# brushless_module_v1.net
KiCad netlist of a schematic drawn in EAGLE
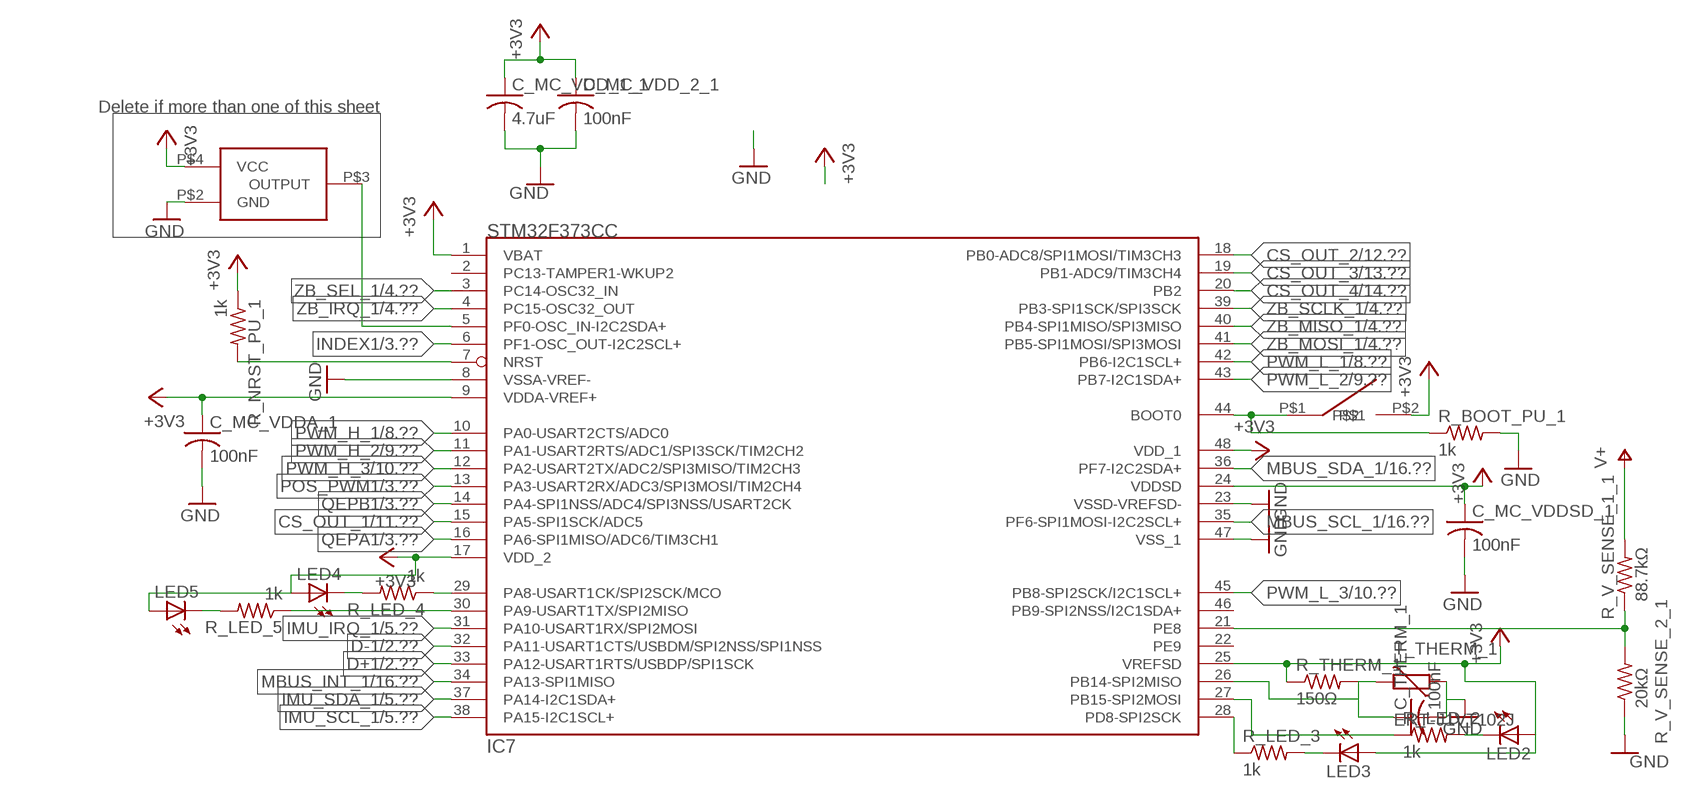
[diagram p0: schematic, sheet 1]
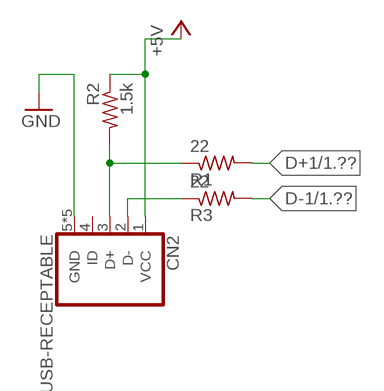
[diagram p1: schematic, sheet 2]
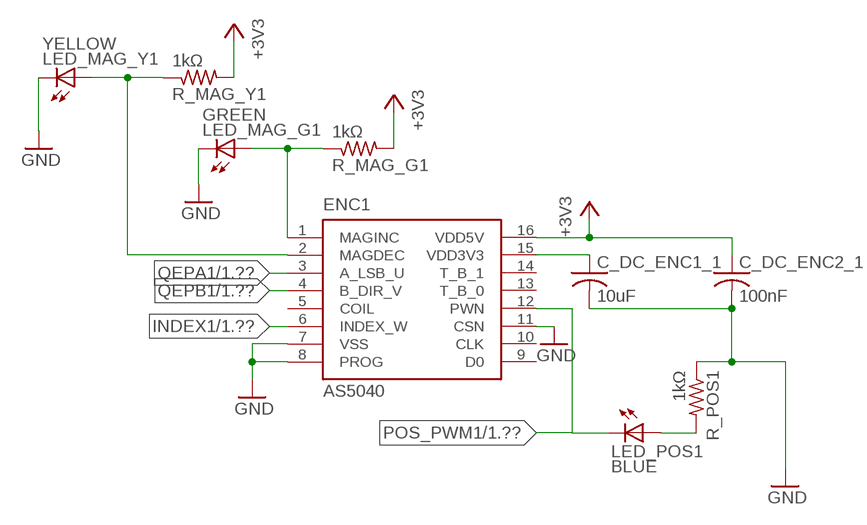
[diagram p2: schematic, sheet 3]
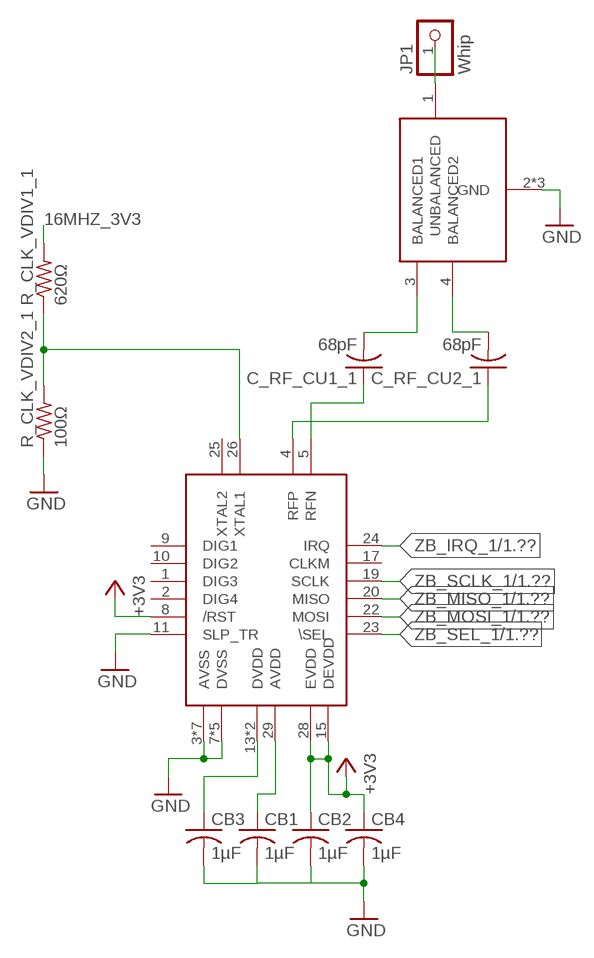
[diagram p3: schematic, sheet 4]
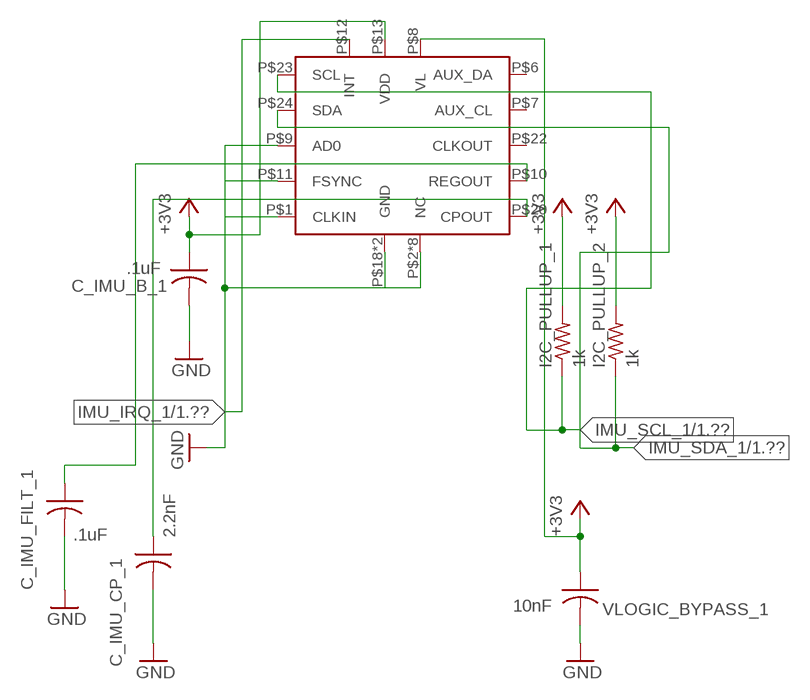
[diagram p4: schematic, sheet 5]
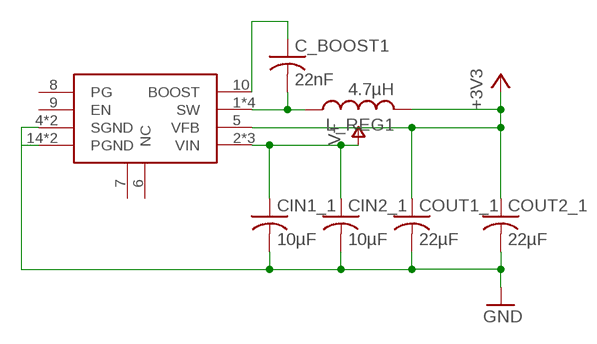
[diagram p5: schematic, sheet 6]
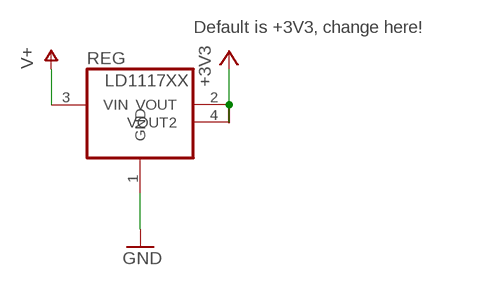
[diagram p6: schematic, sheet 7]
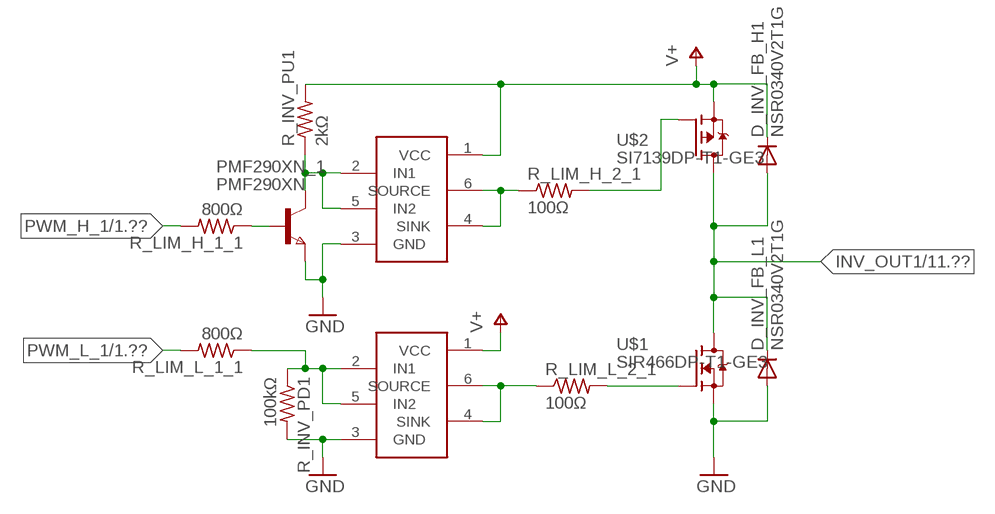
[diagram p7: schematic, sheet 8]
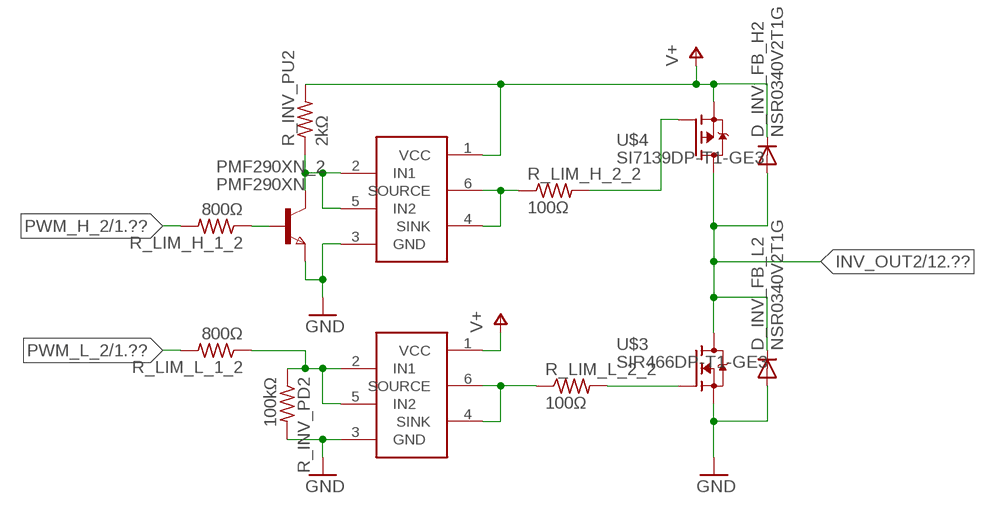
[diagram p8: schematic, sheet 9]
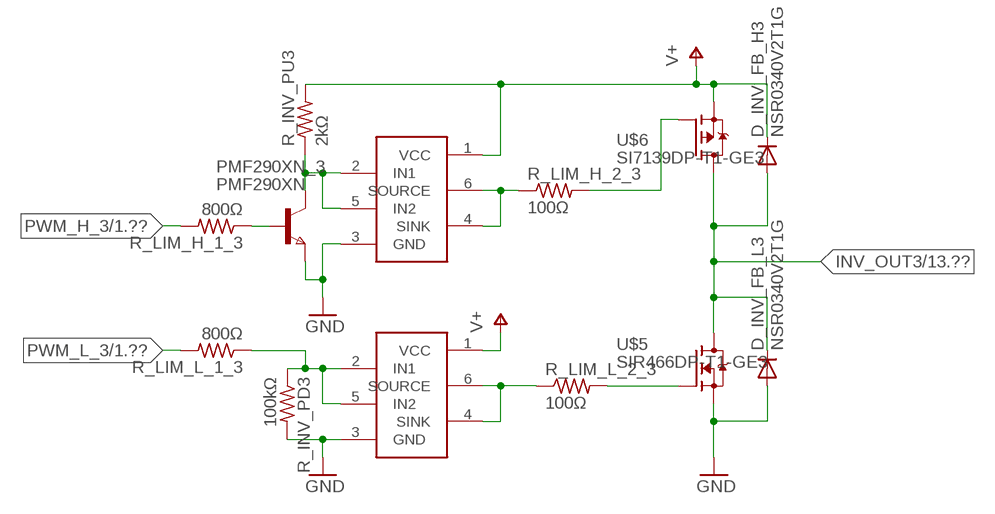
[diagram p9: schematic, sheet 10]
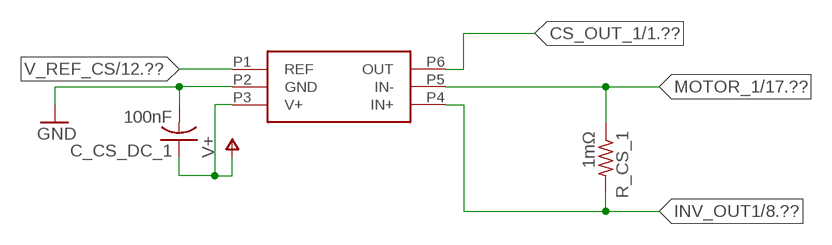
[diagram p10: schematic, sheet 11]
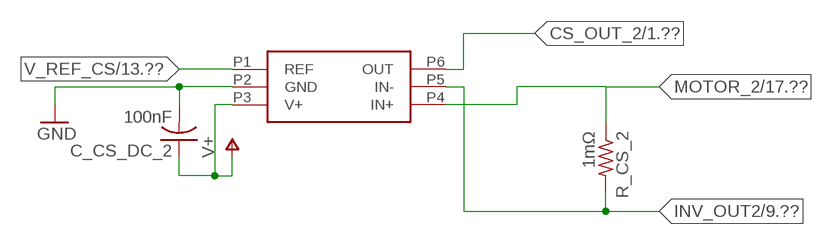
[diagram p11: schematic, sheet 12]
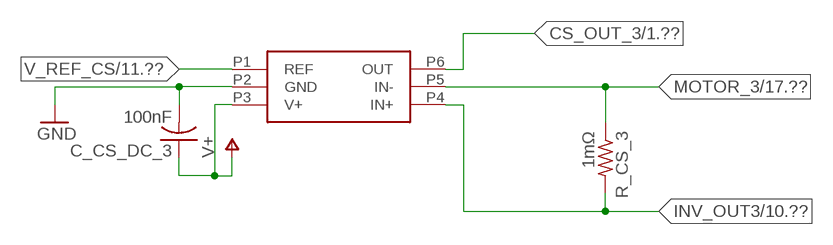
[diagram p12: schematic, sheet 13]
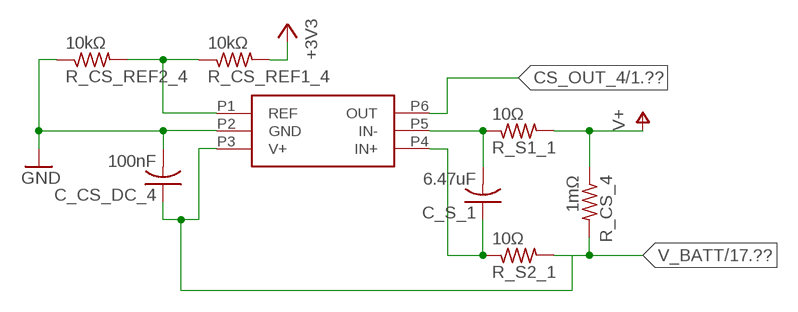
[diagram p13: schematic, sheet 14]
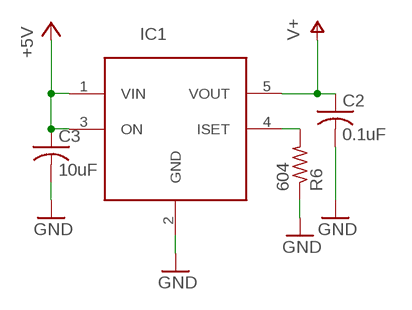
[diagram p14: schematic, sheet 15]
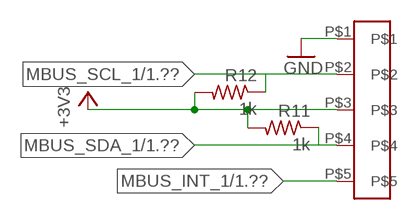
[diagram p15: schematic, sheet 16]
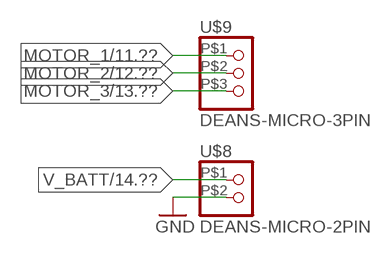
[diagram p16: schematic, sheet 17]

(export (version "E")
  (design (tool "Eeschema 10.0.6"))
  (components
    (comp (ref "CS_3")
      (value "INA21X")
      (footprint "eagle-import:SC70")
      (libsource (lib "eagle-import") (part "INA21X"))
    )
    (comp (ref "C_CS_DC_3")
      (value "100nF")
      (footprint "eagle-import:C0603")
      (libsource (lib "eagle-import") (part "C-USC0603"))
    )
    (comp (ref "R_CS_3")
      (value "1mΩ")
      (footprint "eagle-import:R1206")
      (libsource (lib "eagle-import") (part "R-US_R1206"))
    )
    (comp (ref "D_INV_FB_H3")
      (value "NSR0340V2T1G")
      (footprint "eagle-import:SOD523")
      (libsource (lib "eagle-import") (part "DIODE-SOD523"))
    )
    (comp (ref "D_INV_FB_L3")
      (value "NSR0340V2T1G")
      (footprint "eagle-import:SOD523")
      (libsource (lib "eagle-import") (part "DIODE-SOD523"))
    )
    (comp (ref "PMF290XN_3")
      (value "PMF290XN")
      (footprint "eagle-import:SOT323")
      (libsource (lib "eagle-import") (part "NPNSOT323"))
    )
    (comp (ref "R_INV_PD3")
      (value "100kΩ")
      (footprint "eagle-import:R0603")
      (fields (field (name "PART#") "RNCP0603FTD825RCT-ND"))
      (libsource (lib "eagle-import") (part "R-US_R0603"))
    )
    (comp (ref "R_INV_PU3")
      (value "2kΩ")
      (footprint "eagle-import:R0603")
      (libsource (lib "eagle-import") (part "R-US_R0603"))
    )
    (comp (ref "R_LIM_H_1_3")
      (value "800Ω")
      (footprint "eagle-import:R0603")
      (libsource (lib "eagle-import") (part "R-US_R0603"))
    )
    (comp (ref "R_LIM_H_2_3")
      (value "100Ω")
      (footprint "eagle-import:R0603")
      (libsource (lib "eagle-import") (part "R-US_R0603"))
    )
    (comp (ref "R_LIM_L_1_3")
      (value "800Ω")
      (footprint "eagle-import:R0603")
      (libsource (lib "eagle-import") (part "R-US_R0603"))
    )
    (comp (ref "R_LIM_L_2_3")
      (value "100Ω")
      (footprint "eagle-import:R0603")
      (libsource (lib "eagle-import") (part "R-US_R0603"))
    )
    (comp (ref "U$5")
      (value "SIR466DP-T1-GE3")
      (footprint "eagle-import:S0-8-POWERPAK")
      (libsource (lib "eagle-import") (part "SIR466DP-T1-GE3"))
    )
    (comp (ref "U$6")
      (value "SI7139DP-T1-GE3")
      (footprint "eagle-import:S0-8-POWERPAK")
      (libsource (lib "eagle-import") (part "SI7139DP-T1-GE3"))
    )
    (comp (ref "ZXGD3004E6_H_3")
      (value "ZXGD3004E6")
      (footprint "eagle-import:SOT23-6")
      (libsource (lib "eagle-import") (part "ZXGD3004E6"))
    )
    (comp (ref "ZXGD3004E6_L_3")
      (value "ZXGD3004E6")
      (footprint "eagle-import:SOT23-6")
      (libsource (lib "eagle-import") (part "ZXGD3004E6"))
    )
    (comp (ref "CN2")
      (value "USB-RECEPTABLE")
      (footprint "eagle-import:FCI-10103594-0001LF")
      (libsource (lib "eagle-import") (part "USB-RECEPTABLE"))
    )
    (comp (ref "R1")
      (value "22")
      (footprint "eagle-import:R0603")
      (libsource (lib "eagle-import") (part "R-US_R0603"))
    )
    (comp (ref "R2")
      (value "1.5k")
      (footprint "eagle-import:R0603")
      (libsource (lib "eagle-import") (part "R-US_R0603"))
    )
    (comp (ref "R3")
      (value "22")
      (footprint "eagle-import:R0603")
      (libsource (lib "eagle-import") (part "R-US_R0603"))
    )
    (comp (ref "D_INV_FB_H2")
      (value "NSR0340V2T1G")
      (footprint "eagle-import:SOD523")
      (libsource (lib "eagle-import") (part "DIODE-SOD523"))
    )
    (comp (ref "D_INV_FB_L2")
      (value "NSR0340V2T1G")
      (footprint "eagle-import:SOD523")
      (libsource (lib "eagle-import") (part "DIODE-SOD523"))
    )
    (comp (ref "PMF290XN_2")
      (value "PMF290XN")
      (footprint "eagle-import:SOT323")
      (libsource (lib "eagle-import") (part "NPNSOT323"))
    )
    (comp (ref "R_INV_PD2")
      (value "100kΩ")
      (footprint "eagle-import:R0603")
      (fields (field (name "PART#") "RNCP0603FTD825RCT-ND"))
      (libsource (lib "eagle-import") (part "R-US_R0603"))
    )
    (comp (ref "R_INV_PU2")
      (value "2kΩ")
      (footprint "eagle-import:R0603")
      (libsource (lib "eagle-import") (part "R-US_R0603"))
    )
    (comp (ref "R_LIM_H_1_2")
      (value "800Ω")
      (footprint "eagle-import:R0603")
      (libsource (lib "eagle-import") (part "R-US_R0603"))
    )
    (comp (ref "R_LIM_H_2_2")
      (value "100Ω")
      (footprint "eagle-import:R0603")
      (libsource (lib "eagle-import") (part "R-US_R0603"))
    )
    (comp (ref "R_LIM_L_1_2")
      (value "800Ω")
      (footprint "eagle-import:R0603")
      (libsource (lib "eagle-import") (part "R-US_R0603"))
    )
    (comp (ref "R_LIM_L_2_2")
      (value "100Ω")
      (footprint "eagle-import:R0603")
      (libsource (lib "eagle-import") (part "R-US_R0603"))
    )
    (comp (ref "U$3")
      (value "SIR466DP-T1-GE3")
      (footprint "eagle-import:S0-8-POWERPAK")
      (libsource (lib "eagle-import") (part "SIR466DP-T1-GE3"))
    )
    (comp (ref "U$4")
      (value "SI7139DP-T1-GE3")
      (footprint "eagle-import:S0-8-POWERPAK")
      (libsource (lib "eagle-import") (part "SI7139DP-T1-GE3"))
    )
    (comp (ref "ZXGD3004E6_H_2")
      (value "ZXGD3004E6")
      (footprint "eagle-import:SOT23-6")
      (libsource (lib "eagle-import") (part "ZXGD3004E6"))
    )
    (comp (ref "ZXGD3004E6_L_2")
      (value "ZXGD3004E6")
      (footprint "eagle-import:SOT23-6")
      (libsource (lib "eagle-import") (part "ZXGD3004E6"))
    )
    (comp (ref "CS_2")
      (value "INA21X")
      (footprint "eagle-import:SC70")
      (libsource (lib "eagle-import") (part "INA21X"))
    )
    (comp (ref "C_CS_DC_2")
      (value "100nF")
      (footprint "eagle-import:C0603")
      (libsource (lib "eagle-import") (part "C-USC0603"))
    )
    (comp (ref "R_CS_2")
      (value "1mΩ")
      (footprint "eagle-import:R1206")
      (libsource (lib "eagle-import") (part "R-US_R1206"))
    )
    (comp (ref "C_DC_ENC1_1")
      (value "10uF")
      (footprint "eagle-import:C0603")
      (libsource (lib "eagle-import") (part "C-USC0603"))
    )
    (comp (ref "C_DC_ENC2_1")
      (value "100nF")
      (footprint "eagle-import:C0603")
      (libsource (lib "eagle-import") (part "C-USC0603"))
    )
    (comp (ref "ENC1")
      (value "AS5040")
      (footprint "eagle-import:SSOP16")
      (libsource (lib "eagle-import") (part "AS5040"))
    )
    (comp (ref "LED_MAG_G1")
      (value "GREEN")
      (footprint "eagle-import:CHIP-LED0603")
      (libsource (lib "eagle-import") (part "LEDCHIP-LED0603"))
    )
    (comp (ref "LED_MAG_Y1")
      (value "YELLOW")
      (footprint "eagle-import:CHIP-LED0603")
      (libsource (lib "eagle-import") (part "LEDCHIP-LED0603"))
    )
    (comp (ref "LED_POS1")
      (value "BLUE")
      (footprint "eagle-import:CHIP-LED0603")
      (libsource (lib "eagle-import") (part "LEDCHIP-LED0603"))
    )
    (comp (ref "R_MAG_G1")
      (value "1kΩ")
      (footprint "eagle-import:R0603")
      (libsource (lib "eagle-import") (part "R-US_R0603"))
    )
    (comp (ref "R_MAG_Y1")
      (value "1kΩ")
      (footprint "eagle-import:R0603")
      (libsource (lib "eagle-import") (part "R-US_R0603"))
    )
    (comp (ref "R_POS1")
      (value "1kΩ")
      (footprint "eagle-import:R0603")
      (libsource (lib "eagle-import") (part "R-US_R0603"))
    )
    (comp (ref "REG")
      (value "LD1117XX")
      (footprint "eagle-import:SOT-223")
      (libsource (lib "eagle-import") (part "LD1117XX"))
    )
    (comp (ref "CIN1_1")
      (value "10µF")
      (footprint "eagle-import:C0805")
      (libsource (lib "eagle-import") (part "C-USC0805"))
    )
    (comp (ref "CIN2_1")
      (value "10µF")
      (footprint "eagle-import:C0805")
      (libsource (lib "eagle-import") (part "C-USC0805"))
    )
    (comp (ref "COUT1_1")
      (value "22µF")
      (footprint "eagle-import:C0603")
      (libsource (lib "eagle-import") (part "C-USC0603"))
    )
    (comp (ref "COUT2_1")
      (value "22µF")
      (footprint "eagle-import:C0603")
      (libsource (lib "eagle-import") (part "C-USC0603"))
    )
    (comp (ref "C_BOOST1")
      (value "22nF")
      (footprint "eagle-import:C0603")
      (libsource (lib "eagle-import") (part "C-USC0603"))
    )
    (comp (ref "L_REG1")
      (value "4.7µH")
      (footprint "eagle-import:VLC5045")
      (libsource (lib "eagle-import") (part "VLC5045"))
    )
    (comp (ref "SW_REG1")
      (value "MCP16323")
      (footprint "eagle-import:QFN16")
      (libsource (lib "eagle-import") (part "MCP16323"))
    )
    (comp (ref "CS_4")
      (value "INA21X")
      (footprint "eagle-import:SC70")
      (libsource (lib "eagle-import") (part "INA21X"))
    )
    (comp (ref "C_CS_DC_4")
      (value "100nF")
      (footprint "eagle-import:C0603")
      (libsource (lib "eagle-import") (part "C-USC0603"))
    )
    (comp (ref "C_S_1")
      (value "6.47uF")
      (footprint "eagle-import:C0603")
      (libsource (lib "eagle-import") (part "C-USC0603"))
    )
    (comp (ref "R_CS_4")
      (value "1mΩ")
      (footprint "eagle-import:R1206")
      (libsource (lib "eagle-import") (part "R-US_R1206"))
    )
    (comp (ref "R_CS_REF1_4")
      (value "10kΩ")
      (footprint "eagle-import:R0603")
      (libsource (lib "eagle-import") (part "R-US_R0603"))
    )
    (comp (ref "R_CS_REF2_4")
      (value "10kΩ")
      (footprint "eagle-import:R0603")
      (libsource (lib "eagle-import") (part "R-US_R0603"))
    )
    (comp (ref "R_S1_1")
      (value "10Ω")
      (footprint "eagle-import:R0603")
      (libsource (lib "eagle-import") (part "R-US_R0603"))
    )
    (comp (ref "R_S2_1")
      (value "10Ω")
      (footprint "eagle-import:R0603")
      (libsource (lib "eagle-import") (part "R-US_R0603"))
    )
    (comp (ref "C_IMU_B_1")
      (value ".1uF")
      (footprint "eagle-import:C0603")
      (libsource (lib "eagle-import") (part "C-USC0603"))
    )
    (comp (ref "C_IMU_CP_1")
      (value "2.2nF")
      (footprint "eagle-import:C0603")
      (libsource (lib "eagle-import") (part "C-USC0603"))
    )
    (comp (ref "C_IMU_FILT_1")
      (value ".1uF")
      (footprint "eagle-import:C0603")
      (libsource (lib "eagle-import") (part "C-USC0603"))
    )
    (comp (ref "I2C_PULLUP_1")
      (value "1k")
      (footprint "eagle-import:R0603")
      (libsource (lib "eagle-import") (part "R-US_R0603"))
    )
    (comp (ref "I2C_PULLUP_2")
      (value "1k")
      (footprint "eagle-import:R0603")
      (libsource (lib "eagle-import") (part "R-US_R0603"))
    )
    (comp (ref "U$10")
      (value "MPU-6050")
      (footprint "eagle-import:QFN24")
      (libsource (lib "eagle-import") (part "MPU-6050"))
    )
    (comp (ref "VLOGIC_BYPASS_1")
      (value "10nF")
      (footprint "eagle-import:C0603")
      (libsource (lib "eagle-import") (part "C-USC0603"))
    )
    (comp (ref "U$8")
      (value "DEANS-MICRO-2PIN")
      (footprint "eagle-import:DEANS-MICRO-2PIN")
      (libsource (lib "eagle-import") (part "DEANS-MICRO-2PIN"))
    )
    (comp (ref "U$9")
      (value "DEANS-MICRO-3PIN")
      (footprint "eagle-import:DEANS-MICRO-3PIN")
      (libsource (lib "eagle-import") (part "DEANS-MICRO-3PIN"))
    )
    (comp (ref "C_MC_VDDA_1")
      (value "100nF")
      (footprint "eagle-import:C0603")
      (libsource (lib "eagle-import") (part "C-USC0603"))
    )
    (comp (ref "C_MC_VDDSD_1")
      (value "100nF")
      (footprint "eagle-import:C0603")
      (libsource (lib "eagle-import") (part "C-USC0603"))
    )
    (comp (ref "C_MC_VDD_1_1")
      (value "4.7uF")
      (footprint "eagle-import:C0603")
      (libsource (lib "eagle-import") (part "C-USC0603"))
    )
    (comp (ref "C_MC_VDD_2_1")
      (value "100nF")
      (footprint "eagle-import:C0603")
      (libsource (lib "eagle-import") (part "C-USC0603"))
    )
    (comp (ref "C_THERM_1")
      (value "100nF")
      (footprint "eagle-import:C0603")
      (libsource (lib "eagle-import") (part "C-USC0603"))
    )
    (comp (ref "IC7")
      (value "STM32F373CC")
      (footprint "eagle-import:LQFP48")
      (libsource (lib "eagle-import") (part "STM32F373CC"))
    )
    (comp (ref "LED2")
      (value "LEDCHIPLED_0603")
      (footprint "eagle-import:CHIPLED_0603")
      (libsource (lib "eagle-import") (part "LEDCHIPLED_0603"))
    )
    (comp (ref "LED3")
      (value "LEDCHIPLED_0603")
      (footprint "eagle-import:CHIPLED_0603")
      (libsource (lib "eagle-import") (part "LEDCHIPLED_0603"))
    )
    (comp (ref "LED4")
      (value "LEDCHIPLED_0603")
      (footprint "eagle-import:CHIPLED_0603")
      (libsource (lib "eagle-import") (part "LEDCHIPLED_0603"))
    )
    (comp (ref "LED5")
      (value "LEDCHIPLED_0603")
      (footprint "eagle-import:CHIPLED_0603")
      (libsource (lib "eagle-import") (part "LEDCHIPLED_0603"))
    )
    (comp (ref "OSC1")
      (value "FOX924B")
      (footprint "eagle-import:4-SMD_5X3.2")
      (libsource (lib "eagle-import") (part "FOX924B"))
    )
    (comp (ref "R_BOOT_PU_1")
      (value "1k")
      (footprint "eagle-import:R0603")
      (libsource (lib "eagle-import") (part "R-US_R0603"))
    )
    (comp (ref "R_LED_2")
      (value "1k")
      (footprint "eagle-import:R0603")
      (libsource (lib "eagle-import") (part "R-US_R0603"))
    )
    (comp (ref "R_LED_3")
      (value "1k")
      (footprint "eagle-import:R0603")
      (libsource (lib "eagle-import") (part "R-US_R0603"))
    )
    (comp (ref "R_LED_4")
      (value "1k")
      (footprint "eagle-import:R0603")
      (libsource (lib "eagle-import") (part "R-US_R0603"))
    )
    (comp (ref "R_LED_5")
      (value "1k")
      (footprint "eagle-import:R0603")
      (libsource (lib "eagle-import") (part "R-US_R0603"))
    )
    (comp (ref "R_NRST_PU_1")
      (value "1k")
      (footprint "eagle-import:R0603")
      (libsource (lib "eagle-import") (part "R-US_R0603"))
    )
    (comp (ref "R_THERM_1")
      (value "150Ω")
      (footprint "eagle-import:R0603")
      (libsource (lib "eagle-import") (part "R-US_R0603"))
    )
    (comp (ref "R_V_SENSE_1_1")
      (value "88.7kΩ")
      (footprint "eagle-import:R0603")
      (libsource (lib "eagle-import") (part "R-US_R0603"))
    )
    (comp (ref "R_V_SENSE_2_1")
      (value "20kΩ")
      (footprint "eagle-import:R0603")
      (libsource (lib "eagle-import") (part "R-US_R0603"))
    )
    (comp (ref "SW1")
      (value "B3U")
      (footprint "eagle-import:B3U")
      (libsource (lib "eagle-import") (part "B3U"))
    )
    (comp (ref "T_THERM_1")
      (value "ERT-J1VT102J")
      (footprint "eagle-import:CT_CN0603")
      (libsource (lib "eagle-import") (part "VARISTORCN0603"))
    )
    (comp (ref "C2")
      (value "0.1uF")
      (footprint "eagle-import:C0603")
      (libsource (lib "eagle-import") (part "C-USC0603"))
    )
    (comp (ref "C3")
      (value "10uF")
      (footprint "eagle-import:C0603")
      (libsource (lib "eagle-import") (part "C-USC0603"))
    )
    (comp (ref "IC1")
      (value "FPF2123")
      (footprint "eagle-import:SOT23-5L")
      (libsource (lib "eagle-import") (part "FPF2123"))
    )
    (comp (ref "R6")
      (value "604")
      (footprint "eagle-import:R0603")
      (libsource (lib "eagle-import") (part "R-US_R0603"))
    )
    (comp (ref "CS_1")
      (value "INA21X")
      (footprint "eagle-import:SC70")
      (libsource (lib "eagle-import") (part "INA21X"))
    )
    (comp (ref "C_CS_DC_1")
      (value "100nF")
      (footprint "eagle-import:C0603")
      (libsource (lib "eagle-import") (part "C-USC0603"))
    )
    (comp (ref "R_CS_1")
      (value "1mΩ")
      (footprint "eagle-import:R1206")
      (libsource (lib "eagle-import") (part "R-US_R1206"))
    )
    (comp (ref "D_INV_FB_H1")
      (value "NSR0340V2T1G")
      (footprint "eagle-import:SOD523")
      (libsource (lib "eagle-import") (part "DIODE-SOD523"))
    )
    (comp (ref "D_INV_FB_L1")
      (value "NSR0340V2T1G")
      (footprint "eagle-import:SOD523")
      (libsource (lib "eagle-import") (part "DIODE-SOD523"))
    )
    (comp (ref "PMF290XN_1")
      (value "PMF290XN")
      (footprint "eagle-import:SOT323")
      (libsource (lib "eagle-import") (part "NPNSOT323"))
    )
    (comp (ref "R_INV_PD1")
      (value "100kΩ")
      (footprint "eagle-import:R0603")
      (fields (field (name "PART#") "RNCP0603FTD825RCT-ND"))
      (libsource (lib "eagle-import") (part "R-US_R0603"))
    )
    (comp (ref "R_INV_PU1")
      (value "2kΩ")
      (footprint "eagle-import:R0603")
      (libsource (lib "eagle-import") (part "R-US_R0603"))
    )
    (comp (ref "R_LIM_H_1_1")
      (value "800Ω")
      (footprint "eagle-import:R0603")
      (libsource (lib "eagle-import") (part "R-US_R0603"))
    )
    (comp (ref "R_LIM_H_2_1")
      (value "100Ω")
      (footprint "eagle-import:R0603")
      (libsource (lib "eagle-import") (part "R-US_R0603"))
    )
    (comp (ref "R_LIM_L_1_1")
      (value "800Ω")
      (footprint "eagle-import:R0603")
      (libsource (lib "eagle-import") (part "R-US_R0603"))
    )
    (comp (ref "R_LIM_L_2_1")
      (value "100Ω")
      (footprint "eagle-import:R0603")
      (libsource (lib "eagle-import") (part "R-US_R0603"))
    )
    (comp (ref "U$1")
      (value "SIR466DP-T1-GE3")
      (footprint "eagle-import:S0-8-POWERPAK")
      (libsource (lib "eagle-import") (part "SIR466DP-T1-GE3"))
    )
    (comp (ref "U$2")
      (value "SI7139DP-T1-GE3")
      (footprint "eagle-import:S0-8-POWERPAK")
      (libsource (lib "eagle-import") (part "SI7139DP-T1-GE3"))
    )
    (comp (ref "ZXGD3004E6_H_1")
      (value "ZXGD3004E6")
      (footprint "eagle-import:SOT23-6")
      (libsource (lib "eagle-import") (part "ZXGD3004E6"))
    )
    (comp (ref "ZXGD3004E6_L_1")
      (value "ZXGD3004E6")
      (footprint "eagle-import:SOT23-6")
      (libsource (lib "eagle-import") (part "ZXGD3004E6"))
    )
    (comp (ref "R11")
      (value "1k")
      (footprint "eagle-import:R0603")
      (libsource (lib "eagle-import") (part "R-US_R0603"))
    )
    (comp (ref "R12")
      (value "1k")
      (footprint "eagle-import:R0603")
      (libsource (lib "eagle-import") (part "R-US_R0603"))
    )
    (comp (ref "U$7")
      (value "050-5")
      (footprint "eagle-import:050-5")
      (libsource (lib "eagle-import") (part "050-5"))
    )
    (comp (ref "BALUN1")
      (value "0896FB15A0100")
      (footprint "eagle-import:0896FB15A0100")
      (libsource (lib "eagle-import") (part "0896FB15A0100"))
    )
    (comp (ref "CB1")
      (value "1µF")
      (footprint "eagle-import:C0603")
      (libsource (lib "eagle-import") (part "C-USC0603"))
    )
    (comp (ref "CB2")
      (value "1µF")
      (footprint "eagle-import:C0603")
      (libsource (lib "eagle-import") (part "C-USC0603"))
    )
    (comp (ref "CB3")
      (value "1µF")
      (footprint "eagle-import:C0603")
      (libsource (lib "eagle-import") (part "C-USC0603"))
    )
    (comp (ref "CB4")
      (value "1µF")
      (footprint "eagle-import:C0603")
      (libsource (lib "eagle-import") (part "C-USC0603"))
    )
    (comp (ref "C_RF_CU1_1")
      (value "68pF")
      (footprint "eagle-import:C0603")
      (libsource (lib "eagle-import") (part "C-USC0603"))
    )
    (comp (ref "C_RF_CU2_1")
      (value "68pF")
      (footprint "eagle-import:C0603")
      (libsource (lib "eagle-import") (part "C-USC0603"))
    )
    (comp (ref "JP1")
      (value "Whip")
      (footprint "eagle-import:1X01M")
      (libsource (lib "eagle-import") (part "PINHD-1X01_2.00"))
    )
    (comp (ref "RADIO1")
      (value "AT86RF")
      (footprint "eagle-import:QFNN32")
      (libsource (lib "eagle-import") (part "AT86RF"))
    )
    (comp (ref "R_CLK_VDIV1_1")
      (value "620Ω")
      (footprint "eagle-import:R0603")
      (libsource (lib "eagle-import") (part "R-US_R0603"))
    )
    (comp (ref "R_CLK_VDIV2_1")
      (value "100Ω")
      (footprint "eagle-import:R0603")
      (libsource (lib "eagle-import") (part "R-US_R0603"))
    )
  )
  (nets
    (net (code "1") (name "+3V3") (class "Default")
      (node (ref "CB2") (pin "1") (pinfunction "1_1") (pintype "passive"))
      (node (ref "CB4") (pin "1") (pinfunction "1_1") (pintype "passive"))
      (node (ref "COUT1_1") (pin "1") (pinfunction "1_1") (pintype "passive"))
      (node (ref "COUT2_1") (pin "1") (pinfunction "1_1") (pintype "passive"))
      (node (ref "C_DC_ENC2_1") (pin "1") (pinfunction "1_1") (pintype "passive"))
      (node (ref "C_IMU_B_1") (pin "1") (pinfunction "1_1") (pintype "passive"))
      (node (ref "C_MC_VDDA_1") (pin "1") (pinfunction "1_1") (pintype "passive"))
      (node (ref "C_MC_VDDSD_1") (pin "1") (pinfunction "1_1") (pintype "passive"))
      (node (ref "C_MC_VDD_1_1") (pin "1") (pinfunction "1_1") (pintype "passive"))
      (node (ref "C_MC_VDD_2_1") (pin "1") (pinfunction "1_1") (pintype "passive"))
      (node (ref "ENC1") (pin "16") (pinfunction "VDD5V_16") (pintype "passive"))
      (node (ref "I2C_PULLUP_1") (pin "2") (pinfunction "2_2") (pintype "passive"))
      (node (ref "I2C_PULLUP_2") (pin "2") (pinfunction "2_2") (pintype "passive"))
      (node (ref "IC7") (pin "1") (pinfunction "VBAT_1") (pintype "power_in"))
      (node (ref "IC7") (pin "17") (pinfunction "VDD_2_17") (pintype "bidirectional"))
      (node (ref "IC7") (pin "24") (pinfunction "VDDSD_24") (pintype "power_in"))
      (node (ref "IC7") (pin "25") (pinfunction "VREFSD_25") (pintype "bidirectional"))
      (node (ref "IC7") (pin "48") (pinfunction "VDD_1_48") (pintype "power_in"))
      (node (ref "IC7") (pin "9") (pinfunction "VDDA-VREF+_9") (pintype "power_in"))
      (node (ref "LED2") (pin "A") (pinfunction "A_A") (pintype "passive"))
      (node (ref "LED3") (pin "A") (pinfunction "A_A") (pintype "passive"))
      (node (ref "LED4") (pin "A") (pinfunction "A_A") (pintype "passive"))
      (node (ref "LED5") (pin "A") (pinfunction "A_A") (pintype "passive"))
      (node (ref "L_REG1") (pin "2") (pinfunction "2_2") (pintype "passive"))
      (node (ref "OSC1") (pin "P$4") (pinfunction "VCC_P$4") (pintype "bidirectional"))
      (node (ref "R11") (pin "2") (pinfunction "2_2") (pintype "passive"))
      (node (ref "R12") (pin "2") (pinfunction "2_2") (pintype "passive"))
      (node (ref "RADIO1") (pin "15") (pinfunction "DEVDD_15") (pintype "power_in"))
      (node (ref "RADIO1") (pin "28") (pinfunction "EVDD_28") (pintype "power_in"))
      (node (ref "RADIO1") (pin "8") (pinfunction "/RST_8") (pintype "input"))
      (node (ref "REG") (pin "2") (pinfunction "VOUT_2") (pintype "output"))
      (node (ref "REG") (pin "4") (pinfunction "VOUT2_4") (pintype "output"))
      (node (ref "R_CS_REF1_4") (pin "2") (pinfunction "2_2") (pintype "passive"))
      (node (ref "R_MAG_G1") (pin "2") (pinfunction "2_2") (pintype "passive"))
      (node (ref "R_MAG_Y1") (pin "2") (pinfunction "2_2") (pintype "passive"))
      (node (ref "R_NRST_PU_1") (pin "1") (pinfunction "1_1") (pintype "passive"))
      (node (ref "R_THERM_1") (pin "1") (pinfunction "1_1") (pintype "passive"))
      (node (ref "SW1") (pin "P$2") (pinfunction "P$2_P$2") (pintype "bidirectional"))
      (node (ref "SW_REG1") (pin "5") (pinfunction "VFB_5") (pintype "bidirectional"))
      (node (ref "U$10") (pin "P$13") (pinfunction "VDD_P$13") (pintype "bidirectional"))
      (node (ref "U$10") (pin "P$8") (pinfunction "VL_P$8") (pintype "bidirectional"))
      (node (ref "U$7") (pin "P$3") (pinfunction "P$3_P$3") (pintype "bidirectional"))
      (node (ref "VLOGIC_BYPASS_1") (pin "1") (pinfunction "1_1") (pintype "passive"))
    )
    (net (code "2") (name "+5V") (class "Default")
      (node (ref "C3") (pin "1") (pinfunction "1_1") (pintype "passive"))
      (node (ref "CN2") (pin "1") (pinfunction "VCC_1") (pintype "bidirectional"))
      (node (ref "IC1") (pin "1") (pinfunction "VIN_1") (pintype "bidirectional"))
      (node (ref "IC1") (pin "3") (pinfunction "ON_3") (pintype "bidirectional"))
      (node (ref "R2") (pin "1") (pinfunction "1_1") (pintype "passive"))
    )
    (net (code "3") (name "16MHZ_3V3") (class "Default")
      (node (ref "IC7") (pin "5") (pinfunction "PF0-OSC_IN-I2C2SDA+_5") (pintype "bidirectional"))
      (node (ref "OSC1") (pin "P$3") (pinfunction "OUTPUT_P$3") (pintype "bidirectional"))
      (node (ref "R_CLK_VDIV1_1") (pin "2") (pinfunction "2_2") (pintype "passive"))
    )
    (net (code "4") (name "CS_OUT_1") (class "Default")
      (node (ref "CS_1") (pin "P6") (pinfunction "OUT_P6") (pintype "output"))
      (node (ref "IC7") (pin "15") (pinfunction "PA5-SPI1SCK/ADC5_15") (pintype "bidirectional"))
    )
    (net (code "5") (name "CS_OUT_2") (class "Default")
      (node (ref "CS_2") (pin "P6") (pinfunction "OUT_P6") (pintype "output"))
      (node (ref "IC7") (pin "18") (pinfunction "PB0-ADC8/SPI1MOSI/TIM3CH3_18") (pintype "bidirectional"))
    )
    (net (code "6") (name "CS_OUT_3") (class "Default")
      (node (ref "CS_3") (pin "P6") (pinfunction "OUT_P6") (pintype "output"))
      (node (ref "IC7") (pin "19") (pinfunction "PB1-ADC9/TIM3CH4_19") (pintype "bidirectional"))
    )
    (net (code "7") (name "CS_OUT_4") (class "Default")
      (node (ref "CS_4") (pin "P6") (pinfunction "OUT_P6") (pintype "output"))
      (node (ref "IC7") (pin "20") (pinfunction "PB2_20") (pintype "bidirectional"))
    )
    (net (code "8") (name "D+1") (class "Default")
      (node (ref "IC7") (pin "33") (pinfunction "PA12-USART1RTS/USBDP/SPI1SCK_33") (pintype "bidirectional"))
      (node (ref "R1") (pin "2") (pinfunction "2_2") (pintype "passive"))
    )
    (net (code "9") (name "D-1") (class "Default")
      (node (ref "IC7") (pin "32") (pinfunction "PA11-USART1CTS/USBDM/SPI2NSS/SPI1NSS_32") (pintype "bidirectional"))
      (node (ref "R3") (pin "2") (pinfunction "2_2") (pintype "passive"))
    )
    (net (code "10") (name "GND") (class "Default")
      (node (ref "BALUN1") (pin "2") (pinfunction "GND_2") (pintype "power_in"))
      (node (ref "BALUN1") (pin "5") (pinfunction "GND_5") (pintype "power_in"))
      (node (ref "BALUN1") (pin "6") (pinfunction "GND_6") (pintype "power_in"))
      (node (ref "C2") (pin "2") (pinfunction "2_2") (pintype "passive"))
      (node (ref "C3") (pin "2") (pinfunction "2_2") (pintype "passive"))
      (node (ref "CB1") (pin "2") (pinfunction "2_2") (pintype "passive"))
      (node (ref "CB2") (pin "2") (pinfunction "2_2") (pintype "passive"))
      (node (ref "CB3") (pin "2") (pinfunction "2_2") (pintype "passive"))
      (node (ref "CB4") (pin "2") (pinfunction "2_2") (pintype "passive"))
      (node (ref "CIN1_1") (pin "2") (pinfunction "2_2") (pintype "passive"))
      (node (ref "CIN2_1") (pin "2") (pinfunction "2_2") (pintype "passive"))
      (node (ref "CN2") (pin "5") (pinfunction "GND_5") (pintype "bidirectional"))
      (node (ref "CN2") (pin "P$1") (pinfunction "GND_P$1") (pintype "bidirectional"))
      (node (ref "CN2") (pin "P$2") (pinfunction "GND_P$2") (pintype "bidirectional"))
      (node (ref "CN2") (pin "P$3") (pinfunction "GND_P$3") (pintype "bidirectional"))
      (node (ref "CN2") (pin "P$4") (pinfunction "GND_P$4") (pintype "bidirectional"))
      (node (ref "COUT1_1") (pin "2") (pinfunction "2_2") (pintype "passive"))
      (node (ref "COUT2_1") (pin "2") (pinfunction "2_2") (pintype "passive"))
      (node (ref "CS_1") (pin "P2") (pinfunction "GND_P2") (pintype "power_in"))
      (node (ref "CS_2") (pin "P2") (pinfunction "GND_P2") (pintype "power_in"))
      (node (ref "CS_3") (pin "P2") (pinfunction "GND_P2") (pintype "power_in"))
      (node (ref "CS_4") (pin "P2") (pinfunction "GND_P2") (pintype "power_in"))
      (node (ref "C_CS_DC_1") (pin "2") (pinfunction "2_2") (pintype "passive"))
      (node (ref "C_CS_DC_2") (pin "2") (pinfunction "2_2") (pintype "passive"))
      (node (ref "C_CS_DC_3") (pin "2") (pinfunction "2_2") (pintype "passive"))
      (node (ref "C_CS_DC_4") (pin "2") (pinfunction "2_2") (pintype "passive"))
      (node (ref "C_DC_ENC1_1") (pin "2") (pinfunction "2_2") (pintype "passive"))
      (node (ref "C_DC_ENC2_1") (pin "2") (pinfunction "2_2") (pintype "passive"))
      (node (ref "C_IMU_B_1") (pin "2") (pinfunction "2_2") (pintype "passive"))
      (node (ref "C_IMU_CP_1") (pin "2") (pinfunction "2_2") (pintype "passive"))
      (node (ref "C_IMU_FILT_1") (pin "2") (pinfunction "2_2") (pintype "passive"))
      (node (ref "C_MC_VDDA_1") (pin "2") (pinfunction "2_2") (pintype "passive"))
      (node (ref "C_MC_VDDSD_1") (pin "2") (pinfunction "2_2") (pintype "passive"))
      (node (ref "C_MC_VDD_1_1") (pin "2") (pinfunction "2_2") (pintype "passive"))
      (node (ref "C_MC_VDD_2_1") (pin "2") (pinfunction "2_2") (pintype "passive"))
      (node (ref "C_THERM_1") (pin "2") (pinfunction "2_2") (pintype "passive"))
      (node (ref "D_INV_FB_L1") (pin "A") (pinfunction "A_A") (pintype "passive"))
      (node (ref "D_INV_FB_L2") (pin "A") (pinfunction "A_A") (pintype "passive"))
      (node (ref "D_INV_FB_L3") (pin "A") (pinfunction "A_A") (pintype "passive"))
      (node (ref "ENC1") (pin "11") (pinfunction "CSN_11") (pintype "input"))
      (node (ref "ENC1") (pin "7") (pinfunction "VSS_7") (pintype "passive"))
      (node (ref "ENC1") (pin "8") (pinfunction "PROG_8") (pintype "input"))
      (node (ref "IC1") (pin "2") (pinfunction "GND_2") (pintype "bidirectional"))
      (node (ref "IC7") (pin "23") (pinfunction "VSSD-VREFSD-_23") (pintype "power_in"))
      (node (ref "IC7") (pin "47") (pinfunction "VSS_1_47") (pintype "power_in"))
      (node (ref "IC7") (pin "8") (pinfunction "VSSA-VREF-_8") (pintype "power_in"))
      (node (ref "LED_MAG_G1") (pin "C") (pinfunction "C_C") (pintype "passive"))
      (node (ref "LED_MAG_Y1") (pin "C") (pinfunction "C_C") (pintype "passive"))
      (node (ref "OSC1") (pin "P$2") (pinfunction "GND_P$2") (pintype "bidirectional"))
      (node (ref "PMF290XN_1") (pin "3") (pinfunction "E_3") (pintype "passive"))
      (node (ref "PMF290XN_2") (pin "3") (pinfunction "E_3") (pintype "passive"))
      (node (ref "PMF290XN_3") (pin "3") (pinfunction "E_3") (pintype "passive"))
      (node (ref "R6") (pin "1") (pinfunction "1_1") (pintype "passive"))
      (node (ref "RADIO1") (pin "11") (pinfunction "SLP_TR_11") (pintype "bidirectional"))
      (node (ref "RADIO1") (pin "12") (pinfunction "DVSS_12") (pintype "power_in"))
      (node (ref "RADIO1") (pin "16") (pinfunction "DVSS_16") (pintype "power_in"))
      (node (ref "RADIO1") (pin "18") (pinfunction "DVSS_18") (pintype "power_in"))
      (node (ref "RADIO1") (pin "21") (pinfunction "DVSS_21") (pintype "power_in"))
      (node (ref "RADIO1") (pin "27") (pinfunction "AVSS_27") (pintype "power_in"))
      (node (ref "RADIO1") (pin "3") (pinfunction "AVSS_3") (pintype "power_in"))
      (node (ref "RADIO1") (pin "30") (pinfunction "AVSS_30") (pintype "power_in"))
      (node (ref "RADIO1") (pin "31") (pinfunction "AVSS_31") (pintype "power_in"))
      (node (ref "RADIO1") (pin "32") (pinfunction "AVSS_32") (pintype "power_in"))
      (node (ref "RADIO1") (pin "6") (pinfunction "AVSS_6") (pintype "power_in"))
      (node (ref "RADIO1") (pin "7") (pinfunction "DVSS_7") (pintype "power_in"))
      (node (ref "RADIO1") (pin "EXP") (pinfunction "AVSS_EXP") (pintype "power_in"))
      (node (ref "REG") (pin "1") (pinfunction "GND_1") (pintype "power_in"))
      (node (ref "R_BOOT_PU_1") (pin "2") (pinfunction "2_2") (pintype "passive"))
      (node (ref "R_CLK_VDIV2_1") (pin "1") (pinfunction "1_1") (pintype "passive"))
      (node (ref "R_CS_REF2_4") (pin "1") (pinfunction "1_1") (pintype "passive"))
      (node (ref "R_INV_PD1") (pin "2") (pinfunction "2_2") (pintype "passive"))
      (node (ref "R_INV_PD2") (pin "2") (pinfunction "2_2") (pintype "passive"))
      (node (ref "R_INV_PD3") (pin "2") (pinfunction "2_2") (pintype "passive"))
      (node (ref "R_POS1") (pin "1") (pinfunction "1_1") (pintype "passive"))
      (node (ref "R_V_SENSE_2_1") (pin "1") (pinfunction "1_1") (pintype "passive"))
      (node (ref "SW_REG1") (pin "14") (pinfunction "PGND_14") (pintype "bidirectional"))
      (node (ref "SW_REG1") (pin "15") (pinfunction "PGND_15") (pintype "bidirectional"))
      (node (ref "SW_REG1") (pin "4") (pinfunction "SGND_4") (pintype "bidirectional"))
      (node (ref "SW_REG1") (pin "TH") (pinfunction "SGND_TH") (pintype "bidirectional"))
      (node (ref "T_THERM_1") (pin "1") (pinfunction "1_1") (pintype "passive"))
      (node (ref "U$1") (pin "1") (pinfunction "S_1") (pintype "passive"))
      (node (ref "U$1") (pin "2") (pinfunction "S_2") (pintype "passive"))
      (node (ref "U$1") (pin "3") (pinfunction "S_3") (pintype "passive"))
      (node (ref "U$10") (pin "P$1") (pinfunction "CLKIN_P$1") (pintype "bidirectional"))
      (node (ref "U$10") (pin "P$11") (pinfunction "FSYNC_P$11") (pintype "bidirectional"))
      (node (ref "U$10") (pin "P$14") (pinfunction "NC_P$14") (pintype "bidirectional"))
      (node (ref "U$10") (pin "P$15") (pinfunction "NC_P$15") (pintype "bidirectional"))
      (node (ref "U$10") (pin "P$16") (pinfunction "NC_P$16") (pintype "bidirectional"))
      (node (ref "U$10") (pin "P$17") (pinfunction "NC_P$17") (pintype "bidirectional"))
      (node (ref "U$10") (pin "P$18") (pinfunction "GND_P$18") (pintype "bidirectional"))
      (node (ref "U$10") (pin "P$2") (pinfunction "NC_P$2") (pintype "bidirectional"))
      (node (ref "U$10") (pin "P$25") (pinfunction "GND_P$25") (pintype "bidirectional"))
      (node (ref "U$10") (pin "P$3") (pinfunction "NC_P$3") (pintype "bidirectional"))
      (node (ref "U$10") (pin "P$4") (pinfunction "NC_P$4") (pintype "bidirectional"))
      (node (ref "U$10") (pin "P$5") (pinfunction "NC_P$5") (pintype "bidirectional"))
      (node (ref "U$10") (pin "P$9") (pinfunction "AD0_P$9") (pintype "bidirectional"))
      (node (ref "U$3") (pin "1") (pinfunction "S_1") (pintype "passive"))
      (node (ref "U$3") (pin "2") (pinfunction "S_2") (pintype "passive"))
      (node (ref "U$3") (pin "3") (pinfunction "S_3") (pintype "passive"))
      (node (ref "U$5") (pin "1") (pinfunction "S_1") (pintype "passive"))
      (node (ref "U$5") (pin "2") (pinfunction "S_2") (pintype "passive"))
      (node (ref "U$5") (pin "3") (pinfunction "S_3") (pintype "passive"))
      (node (ref "U$7") (pin "P$1") (pinfunction "P$1_P$1") (pintype "bidirectional"))
      (node (ref "U$8") (pin "P$2") (pinfunction "2_P$2") (pintype "passive"))
      (node (ref "VLOGIC_BYPASS_1") (pin "2") (pinfunction "2_2") (pintype "passive"))
      (node (ref "ZXGD3004E6_H_1") (pin "3") (pinfunction "GND_3") (pintype "power_in"))
      (node (ref "ZXGD3004E6_H_2") (pin "3") (pinfunction "GND_3") (pintype "power_in"))
      (node (ref "ZXGD3004E6_H_3") (pin "3") (pinfunction "GND_3") (pintype "power_in"))
      (node (ref "ZXGD3004E6_L_1") (pin "3") (pinfunction "GND_3") (pintype "power_in"))
      (node (ref "ZXGD3004E6_L_2") (pin "3") (pinfunction "GND_3") (pintype "power_in"))
      (node (ref "ZXGD3004E6_L_3") (pin "3") (pinfunction "GND_3") (pintype "power_in"))
    )
    (net (code "11") (name "IMU_IRQ_1") (class "Default")
      (node (ref "IC7") (pin "31") (pinfunction "PA10-USART1RX/SPI2MOSI_31") (pintype "bidirectional"))
      (node (ref "U$10") (pin "P$12") (pinfunction "INT_P$12") (pintype "bidirectional"))
    )
    (net (code "12") (name "IMU_SCL_1") (class "Default")
      (node (ref "I2C_PULLUP_1") (pin "1") (pinfunction "1_1") (pintype "passive"))
      (node (ref "IC7") (pin "38") (pinfunction "PA15-I2C1SCL+_38") (pintype "bidirectional"))
      (node (ref "U$10") (pin "P$23") (pinfunction "SCL_P$23") (pintype "bidirectional"))
    )
    (net (code "13") (name "IMU_SDA_1") (class "Default")
      (node (ref "I2C_PULLUP_2") (pin "1") (pinfunction "1_1") (pintype "passive"))
      (node (ref "IC7") (pin "37") (pinfunction "PA14-I2C1SDA+_37") (pintype "bidirectional"))
      (node (ref "U$10") (pin "P$24") (pinfunction "SDA_P$24") (pintype "bidirectional"))
    )
    (net (code "14") (name "INDEX1") (class "Default")
      (node (ref "ENC1") (pin "6") (pinfunction "INDEX_W_6") (pintype "output"))
      (node (ref "IC7") (pin "6") (pinfunction "PF1-OSC_OUT-I2C2SCL+_6") (pintype "bidirectional"))
    )
    (net (code "15") (name "INV_OUT1") (class "Default")
      (node (ref "CS_1") (pin "P4") (pinfunction "IN+_P4") (pintype "input"))
      (node (ref "D_INV_FB_H1") (pin "A") (pinfunction "A_A") (pintype "passive"))
      (node (ref "D_INV_FB_L1") (pin "C") (pinfunction "C_C") (pintype "passive"))
      (node (ref "R_CS_1") (pin "2") (pinfunction "2_2") (pintype "passive"))
      (node (ref "U$1") (pin "5") (pinfunction "D_5") (pintype "passive"))
      (node (ref "U$1") (pin "6") (pinfunction "D_6") (pintype "passive"))
      (node (ref "U$1") (pin "7") (pinfunction "D_7") (pintype "passive"))
      (node (ref "U$1") (pin "8") (pinfunction "D_8") (pintype "passive"))
      (node (ref "U$1") (pin "P$1") (pinfunction "D_P$1") (pintype "passive"))
      (node (ref "U$2") (pin "5") (pinfunction "D_5") (pintype "passive"))
      (node (ref "U$2") (pin "6") (pinfunction "D_6") (pintype "passive"))
      (node (ref "U$2") (pin "7") (pinfunction "D_7") (pintype "passive"))
      (node (ref "U$2") (pin "8") (pinfunction "D_8") (pintype "passive"))
      (node (ref "U$2") (pin "P$1") (pinfunction "D_P$1") (pintype "passive"))
    )
    (net (code "16") (name "INV_OUT2") (class "Default")
      (node (ref "CS_2") (pin "P5") (pinfunction "IN-_P5") (pintype "input"))
      (node (ref "D_INV_FB_H2") (pin "A") (pinfunction "A_A") (pintype "passive"))
      (node (ref "D_INV_FB_L2") (pin "C") (pinfunction "C_C") (pintype "passive"))
      (node (ref "R_CS_2") (pin "2") (pinfunction "2_2") (pintype "passive"))
      (node (ref "U$3") (pin "5") (pinfunction "D_5") (pintype "passive"))
      (node (ref "U$3") (pin "6") (pinfunction "D_6") (pintype "passive"))
      (node (ref "U$3") (pin "7") (pinfunction "D_7") (pintype "passive"))
      (node (ref "U$3") (pin "8") (pinfunction "D_8") (pintype "passive"))
      (node (ref "U$3") (pin "P$1") (pinfunction "D_P$1") (pintype "passive"))
      (node (ref "U$4") (pin "5") (pinfunction "D_5") (pintype "passive"))
      (node (ref "U$4") (pin "6") (pinfunction "D_6") (pintype "passive"))
      (node (ref "U$4") (pin "7") (pinfunction "D_7") (pintype "passive"))
      (node (ref "U$4") (pin "8") (pinfunction "D_8") (pintype "passive"))
      (node (ref "U$4") (pin "P$1") (pinfunction "D_P$1") (pintype "passive"))
    )
    (net (code "17") (name "INV_OUT3") (class "Default")
      (node (ref "CS_3") (pin "P4") (pinfunction "IN+_P4") (pintype "input"))
      (node (ref "D_INV_FB_H3") (pin "A") (pinfunction "A_A") (pintype "passive"))
      (node (ref "D_INV_FB_L3") (pin "C") (pinfunction "C_C") (pintype "passive"))
      (node (ref "R_CS_3") (pin "2") (pinfunction "2_2") (pintype "passive"))
      (node (ref "U$5") (pin "5") (pinfunction "D_5") (pintype "passive"))
      (node (ref "U$5") (pin "6") (pinfunction "D_6") (pintype "passive"))
      (node (ref "U$5") (pin "7") (pinfunction "D_7") (pintype "passive"))
      (node (ref "U$5") (pin "8") (pinfunction "D_8") (pintype "passive"))
      (node (ref "U$5") (pin "P$1") (pinfunction "D_P$1") (pintype "passive"))
      (node (ref "U$6") (pin "5") (pinfunction "D_5") (pintype "passive"))
      (node (ref "U$6") (pin "6") (pinfunction "D_6") (pintype "passive"))
      (node (ref "U$6") (pin "7") (pinfunction "D_7") (pintype "passive"))
      (node (ref "U$6") (pin "8") (pinfunction "D_8") (pintype "passive"))
      (node (ref "U$6") (pin "P$1") (pinfunction "D_P$1") (pintype "passive"))
    )
    (net (code "18") (name "MBUS_INT_1") (class "Default")
      (node (ref "IC7") (pin "34") (pinfunction "PA13-SPI1MISO_34") (pintype "bidirectional"))
      (node (ref "U$7") (pin "P$5") (pinfunction "P$5_P$5") (pintype "bidirectional"))
    )
    (net (code "19") (name "MBUS_SCL_1") (class "Default")
      (node (ref "IC7") (pin "35") (pinfunction "PF6-SPI1MOSI-I2C2SCL+_35") (pintype "bidirectional"))
      (node (ref "R12") (pin "1") (pinfunction "1_1") (pintype "passive"))
      (node (ref "U$7") (pin "P$2") (pinfunction "P$2_P$2") (pintype "bidirectional"))
    )
    (net (code "20") (name "MBUS_SDA_1") (class "Default")
      (node (ref "IC7") (pin "36") (pinfunction "PF7-I2C2SDA+_36") (pintype "bidirectional"))
      (node (ref "R11") (pin "1") (pinfunction "1_1") (pintype "passive"))
      (node (ref "U$7") (pin "P$4") (pinfunction "P$4_P$4") (pintype "bidirectional"))
    )
    (net (code "21") (name "MOTOR_1") (class "Default")
      (node (ref "CS_1") (pin "P5") (pinfunction "IN-_P5") (pintype "input"))
      (node (ref "R_CS_1") (pin "1") (pinfunction "1_1") (pintype "passive"))
      (node (ref "U$9") (pin "P$1") (pinfunction "1_P$1") (pintype "passive"))
    )
    (net (code "22") (name "MOTOR_2") (class "Default")
      (node (ref "CS_2") (pin "P4") (pinfunction "IN+_P4") (pintype "input"))
      (node (ref "R_CS_2") (pin "1") (pinfunction "1_1") (pintype "passive"))
      (node (ref "U$9") (pin "P$2") (pinfunction "2_P$2") (pintype "passive"))
    )
    (net (code "23") (name "MOTOR_3") (class "Default")
      (node (ref "CS_3") (pin "P5") (pinfunction "IN-_P5") (pintype "input"))
      (node (ref "R_CS_3") (pin "1") (pinfunction "1_1") (pintype "passive"))
      (node (ref "U$9") (pin "P$3") (pinfunction "3_P$3") (pintype "passive"))
    )
    (net (code "24") (name "Net-(BALUN1-BALANCED1)") (class "Default")
      (node (ref "BALUN1") (pin "3") (pinfunction "BALANCED1_3") (pintype "bidirectional"))
      (node (ref "C_RF_CU1_1") (pin "2") (pinfunction "2_2") (pintype "passive"))
    )
    (net (code "25") (name "Net-(BALUN1-BALANCED2)") (class "Default")
      (node (ref "BALUN1") (pin "4") (pinfunction "BALANCED2_4") (pintype "bidirectional"))
      (node (ref "C_RF_CU2_1") (pin "2") (pinfunction "2_2") (pintype "passive"))
    )
    (net (code "26") (name "Net-(BALUN1-UNBALANCED)") (class "Default")
      (node (ref "BALUN1") (pin "1") (pinfunction "UNBALANCED_1") (pintype "bidirectional"))
      (node (ref "JP1") (pin "1") (pinfunction "1_1") (pintype "passive"))
    )
    (net (code "27") (name "Net-(CB3-Pad1)") (class "Default")
      (node (ref "CB3") (pin "1") (pinfunction "1_1") (pintype "passive"))
      (node (ref "RADIO1") (pin "13") (pinfunction "DVDD_13") (pintype "power_in"))
      (node (ref "RADIO1") (pin "14") (pinfunction "DVDD_14") (pintype "power_in"))
    )
    (net (code "28") (name "Net-(CN2-D+)") (class "Default")
      (node (ref "CN2") (pin "3") (pinfunction "D+_3") (pintype "bidirectional"))
      (node (ref "R1") (pin "1") (pinfunction "1_1") (pintype "passive"))
      (node (ref "R2") (pin "2") (pinfunction "2_2") (pintype "passive"))
    )
    (net (code "29") (name "Net-(CN2-D-)") (class "Default")
      (node (ref "CN2") (pin "2") (pinfunction "D-_2") (pintype "bidirectional"))
      (node (ref "R3") (pin "1") (pinfunction "1_1") (pintype "passive"))
    )
    (net (code "30") (name "Net-(CS_4-IN+)") (class "Default")
      (node (ref "CS_4") (pin "P4") (pinfunction "IN+_P4") (pintype "input"))
      (node (ref "C_S_1") (pin "1") (pinfunction "1_1") (pintype "passive"))
      (node (ref "R_S2_1") (pin "1") (pinfunction "1_1") (pintype "passive"))
    )
    (net (code "31") (name "Net-(CS_4-IN-)") (class "Default")
      (node (ref "CS_4") (pin "P5") (pinfunction "IN-_P5") (pintype "input"))
      (node (ref "C_S_1") (pin "2") (pinfunction "2_2") (pintype "passive"))
      (node (ref "R_S1_1") (pin "1") (pinfunction "1_1") (pintype "passive"))
    )
    (net (code "32") (name "Net-(C_BOOST1-Pad2)") (class "Default")
      (node (ref "C_BOOST1") (pin "2") (pinfunction "2_2") (pintype "passive"))
      (node (ref "L_REG1") (pin "1") (pinfunction "1_1") (pintype "passive"))
      (node (ref "SW_REG1") (pin "1") (pinfunction "SW_1") (pintype "bidirectional"))
      (node (ref "SW_REG1") (pin "12") (pinfunction "SW_12") (pintype "bidirectional"))
      (node (ref "SW_REG1") (pin "13") (pinfunction "SW_13") (pintype "bidirectional"))
      (node (ref "SW_REG1") (pin "16") (pinfunction "SW_16") (pintype "bidirectional"))
    )
    (net (code "33") (name "Net-(ENC1-MAGDEC)") (class "Default")
      (node (ref "ENC1") (pin "2") (pinfunction "MAGDEC_2") (pintype "tri_state"))
      (node (ref "LED_MAG_Y1") (pin "A") (pinfunction "A_A") (pintype "passive"))
      (node (ref "R_MAG_Y1") (pin "1") (pinfunction "1_1") (pintype "passive"))
    )
    (net (code "34") (name "Net-(ENC1-MAGINC)") (class "Default")
      (node (ref "ENC1") (pin "1") (pinfunction "MAGINC_1") (pintype "tri_state"))
      (node (ref "LED_MAG_G1") (pin "A") (pinfunction "A_A") (pintype "passive"))
      (node (ref "R_MAG_G1") (pin "1") (pinfunction "1_1") (pintype "passive"))
    )
    (net (code "35") (name "Net-(ENC1-VDD3V3)") (class "Default")
      (node (ref "C_DC_ENC1_1") (pin "1") (pinfunction "1_1") (pintype "passive"))
      (node (ref "ENC1") (pin "15") (pinfunction "VDD3V3_15") (pintype "passive"))
    )
    (net (code "36") (name "Net-(IC1-ISET)") (class "Default")
      (node (ref "IC1") (pin "4") (pinfunction "ISET_4") (pintype "bidirectional"))
      (node (ref "R6") (pin "2") (pinfunction "2_2") (pintype "passive"))
    )
    (net (code "37") (name "Net-(IC7-BOOT0)") (class "Default")
      (node (ref "IC7") (pin "44") (pinfunction "BOOT0_44") (pintype "input"))
      (node (ref "R_BOOT_PU_1") (pin "1") (pinfunction "1_1") (pintype "passive"))
      (node (ref "SW1") (pin "P$1") (pinfunction "P$1_P$1") (pintype "bidirectional"))
    )
    (net (code "38") (name "Net-(IC7-NRST)") (class "Default")
      (node (ref "IC7") (pin "7") (pinfunction "NRST_7") (pintype "bidirectional"))
      (node (ref "R_NRST_PU_1") (pin "2") (pinfunction "2_2") (pintype "passive"))
    )
    (net (code "39") (name "Net-(IC7-PA8-USART1CK{slash}SPI2SCK{slash}MCO)") (class "Default")
      (node (ref "IC7") (pin "29") (pinfunction "PA8-USART1CK/SPI2SCK/MCO_29") (pintype "bidirectional"))
      (node (ref "R_LED_4") (pin "1") (pinfunction "1_1") (pintype "passive"))
    )
    (net (code "40") (name "Net-(IC7-PA9-USART1TX{slash}SPI2MISO)") (class "Default")
      (node (ref "IC7") (pin "30") (pinfunction "PA9-USART1TX/SPI2MISO_30") (pintype "bidirectional"))
      (node (ref "R_LED_5") (pin "1") (pinfunction "1_1") (pintype "passive"))
    )
    (net (code "41") (name "Net-(IC7-PB14-SPI2MISO)") (class "Default")
      (node (ref "C_THERM_1") (pin "1") (pinfunction "1_1") (pintype "passive"))
      (node (ref "IC7") (pin "26") (pinfunction "PB14-SPI2MISO_26") (pintype "bidirectional"))
      (node (ref "R_THERM_1") (pin "2") (pinfunction "2_2") (pintype "passive"))
      (node (ref "T_THERM_1") (pin "2") (pinfunction "2_2") (pintype "passive"))
    )
    (net (code "42") (name "Net-(IC7-PB15-SPI2MOSI)") (class "Default")
      (node (ref "IC7") (pin "27") (pinfunction "PB15-SPI2MOSI_27") (pintype "bidirectional"))
      (node (ref "R_LED_2") (pin "1") (pinfunction "1_1") (pintype "passive"))
    )
    (net (code "43") (name "Net-(IC7-PD8-SPI2SCK)") (class "Default")
      (node (ref "IC7") (pin "28") (pinfunction "PD8-SPI2SCK_28") (pintype "bidirectional"))
      (node (ref "R_LED_3") (pin "1") (pinfunction "1_1") (pintype "passive"))
    )
    (net (code "44") (name "Net-(IC7-PE8)") (class "Default")
      (node (ref "IC7") (pin "21") (pinfunction "PE8_21") (pintype "bidirectional"))
      (node (ref "R_V_SENSE_1_1") (pin "1") (pinfunction "1_1") (pintype "passive"))
      (node (ref "R_V_SENSE_2_1") (pin "2") (pinfunction "2_2") (pintype "passive"))
    )
    (net (code "45") (name "Net-(LED2-PadC)") (class "Default")
      (node (ref "LED2") (pin "C") (pinfunction "C_C") (pintype "passive"))
      (node (ref "R_LED_2") (pin "2") (pinfunction "2_2") (pintype "passive"))
    )
    (net (code "46") (name "Net-(LED3-PadC)") (class "Default")
      (node (ref "LED3") (pin "C") (pinfunction "C_C") (pintype "passive"))
      (node (ref "R_LED_3") (pin "2") (pinfunction "2_2") (pintype "passive"))
    )
    (net (code "47") (name "Net-(LED4-PadC)") (class "Default")
      (node (ref "LED4") (pin "C") (pinfunction "C_C") (pintype "passive"))
      (node (ref "R_LED_4") (pin "2") (pinfunction "2_2") (pintype "passive"))
    )
    (net (code "48") (name "Net-(LED5-PadC)") (class "Default")
      (node (ref "LED5") (pin "C") (pinfunction "C_C") (pintype "passive"))
      (node (ref "R_LED_5") (pin "2") (pinfunction "2_2") (pintype "passive"))
    )
    (net (code "49") (name "Net-(LED_POS1-PadA)") (class "Default")
      (node (ref "LED_POS1") (pin "A") (pinfunction "A_A") (pintype "passive"))
      (node (ref "R_POS1") (pin "2") (pinfunction "2_2") (pintype "passive"))
    )
    (net (code "50") (name "Net-(PMF290XN_1-B)") (class "Default")
      (node (ref "PMF290XN_1") (pin "2") (pinfunction "B_2") (pintype "passive"))
      (node (ref "R_LIM_H_1_1") (pin "1") (pinfunction "1_1") (pintype "passive"))
    )
    (net (code "51") (name "Net-(PMF290XN_1-C)") (class "Default")
      (node (ref "PMF290XN_1") (pin "1") (pinfunction "C_1") (pintype "passive"))
      (node (ref "R_INV_PU1") (pin "1") (pinfunction "1_1") (pintype "passive"))
      (node (ref "ZXGD3004E6_H_1") (pin "2") (pinfunction "IN1_2") (pintype "input"))
      (node (ref "ZXGD3004E6_H_1") (pin "5") (pinfunction "IN2_5") (pintype "input"))
    )
    (net (code "52") (name "Net-(PMF290XN_2-B)") (class "Default")
      (node (ref "PMF290XN_2") (pin "2") (pinfunction "B_2") (pintype "passive"))
      (node (ref "R_LIM_H_1_2") (pin "1") (pinfunction "1_1") (pintype "passive"))
    )
    (net (code "53") (name "Net-(PMF290XN_2-C)") (class "Default")
      (node (ref "PMF290XN_2") (pin "1") (pinfunction "C_1") (pintype "passive"))
      (node (ref "R_INV_PU2") (pin "1") (pinfunction "1_1") (pintype "passive"))
      (node (ref "ZXGD3004E6_H_2") (pin "2") (pinfunction "IN1_2") (pintype "input"))
      (node (ref "ZXGD3004E6_H_2") (pin "5") (pinfunction "IN2_5") (pintype "input"))
    )
    (net (code "54") (name "Net-(PMF290XN_3-B)") (class "Default")
      (node (ref "PMF290XN_3") (pin "2") (pinfunction "B_2") (pintype "passive"))
      (node (ref "R_LIM_H_1_3") (pin "1") (pinfunction "1_1") (pintype "passive"))
    )
    (net (code "55") (name "Net-(PMF290XN_3-C)") (class "Default")
      (node (ref "PMF290XN_3") (pin "1") (pinfunction "C_1") (pintype "passive"))
      (node (ref "R_INV_PU3") (pin "1") (pinfunction "1_1") (pintype "passive"))
      (node (ref "ZXGD3004E6_H_3") (pin "2") (pinfunction "IN1_2") (pintype "input"))
      (node (ref "ZXGD3004E6_H_3") (pin "5") (pinfunction "IN2_5") (pintype "input"))
    )
    (net (code "56") (name "Net-(RADIO1-AVDD)") (class "Default")
      (node (ref "CB1") (pin "1") (pinfunction "1_1") (pintype "passive"))
      (node (ref "RADIO1") (pin "29") (pinfunction "AVDD_29") (pintype "power_in"))
    )
    (net (code "57") (name "Net-(RADIO1-RFN)") (class "Default")
      (node (ref "C_RF_CU1_1") (pin "1") (pinfunction "1_1") (pintype "passive"))
      (node (ref "RADIO1") (pin "5") (pinfunction "RFN_5") (pintype "bidirectional"))
    )
    (net (code "58") (name "Net-(RADIO1-RFP)") (class "Default")
      (node (ref "C_RF_CU2_1") (pin "1") (pinfunction "1_1") (pintype "passive"))
      (node (ref "RADIO1") (pin "4") (pinfunction "RFP_4") (pintype "bidirectional"))
    )
    (net (code "59") (name "Net-(RADIO1-XTAL1)") (class "Default")
      (node (ref "RADIO1") (pin "26") (pinfunction "XTAL1_26") (pintype "bidirectional"))
      (node (ref "R_CLK_VDIV1_1") (pin "1") (pinfunction "1_1") (pintype "passive"))
      (node (ref "R_CLK_VDIV2_1") (pin "2") (pinfunction "2_2") (pintype "passive"))
    )
    (net (code "60") (name "Net-(SW_REG1-BOOST)") (class "Default")
      (node (ref "C_BOOST1") (pin "1") (pinfunction "1_1") (pintype "passive"))
      (node (ref "SW_REG1") (pin "10") (pinfunction "BOOST_10") (pintype "bidirectional"))
    )
    (net (code "61") (name "Net-(U$1-G)") (class "Default")
      (node (ref "R_LIM_L_2_1") (pin "2") (pinfunction "2_2") (pintype "passive"))
      (node (ref "U$1") (pin "4") (pinfunction "G_4") (pintype "passive"))
    )
    (net (code "62") (name "Net-(U$2-G)") (class "Default")
      (node (ref "R_LIM_H_2_1") (pin "2") (pinfunction "2_2") (pintype "passive"))
      (node (ref "U$2") (pin "4") (pinfunction "G_4") (pintype "passive"))
    )
    (net (code "63") (name "Net-(U$3-G)") (class "Default")
      (node (ref "R_LIM_L_2_2") (pin "2") (pinfunction "2_2") (pintype "passive"))
      (node (ref "U$3") (pin "4") (pinfunction "G_4") (pintype "passive"))
    )
    (net (code "64") (name "Net-(U$4-G)") (class "Default")
      (node (ref "R_LIM_H_2_2") (pin "2") (pinfunction "2_2") (pintype "passive"))
      (node (ref "U$4") (pin "4") (pinfunction "G_4") (pintype "passive"))
    )
    (net (code "65") (name "Net-(U$5-G)") (class "Default")
      (node (ref "R_LIM_L_2_3") (pin "2") (pinfunction "2_2") (pintype "passive"))
      (node (ref "U$5") (pin "4") (pinfunction "G_4") (pintype "passive"))
    )
    (net (code "66") (name "Net-(U$6-G)") (class "Default")
      (node (ref "R_LIM_H_2_3") (pin "2") (pinfunction "2_2") (pintype "passive"))
      (node (ref "U$6") (pin "4") (pinfunction "G_4") (pintype "passive"))
    )
    (net (code "67") (name "Net-(U$10-CPOUT)") (class "Default")
      (node (ref "C_IMU_CP_1") (pin "1") (pinfunction "1_1") (pintype "passive"))
      (node (ref "U$10") (pin "P$20") (pinfunction "CPOUT_P$20") (pintype "bidirectional"))
    )
    (net (code "68") (name "Net-(U$10-REGOUT)") (class "Default")
      (node (ref "C_IMU_FILT_1") (pin "1") (pinfunction "1_1") (pintype "passive"))
      (node (ref "U$10") (pin "P$10") (pinfunction "REGOUT_P$10") (pintype "bidirectional"))
    )
    (net (code "69") (name "Net-(ZXGD3004E6_H_1-SINK)") (class "Default")
      (node (ref "R_LIM_H_2_1") (pin "1") (pinfunction "1_1") (pintype "passive"))
      (node (ref "ZXGD3004E6_H_1") (pin "4") (pinfunction "SINK_4") (pintype "output"))
      (node (ref "ZXGD3004E6_H_1") (pin "6") (pinfunction "SOURCE_6") (pintype "output"))
    )
    (net (code "70") (name "Net-(ZXGD3004E6_H_2-SINK)") (class "Default")
      (node (ref "R_LIM_H_2_2") (pin "1") (pinfunction "1_1") (pintype "passive"))
      (node (ref "ZXGD3004E6_H_2") (pin "4") (pinfunction "SINK_4") (pintype "output"))
      (node (ref "ZXGD3004E6_H_2") (pin "6") (pinfunction "SOURCE_6") (pintype "output"))
    )
    (net (code "71") (name "Net-(ZXGD3004E6_H_3-SINK)") (class "Default")
      (node (ref "R_LIM_H_2_3") (pin "1") (pinfunction "1_1") (pintype "passive"))
      (node (ref "ZXGD3004E6_H_3") (pin "4") (pinfunction "SINK_4") (pintype "output"))
      (node (ref "ZXGD3004E6_H_3") (pin "6") (pinfunction "SOURCE_6") (pintype "output"))
    )
    (net (code "72") (name "Net-(ZXGD3004E6_L_1-IN1)") (class "Default")
      (node (ref "R_INV_PD1") (pin "1") (pinfunction "1_1") (pintype "passive"))
      (node (ref "R_LIM_L_1_1") (pin "1") (pinfunction "1_1") (pintype "passive"))
      (node (ref "ZXGD3004E6_L_1") (pin "2") (pinfunction "IN1_2") (pintype "input"))
      (node (ref "ZXGD3004E6_L_1") (pin "5") (pinfunction "IN2_5") (pintype "input"))
    )
    (net (code "73") (name "Net-(ZXGD3004E6_L_1-SINK)") (class "Default")
      (node (ref "R_LIM_L_2_1") (pin "1") (pinfunction "1_1") (pintype "passive"))
      (node (ref "ZXGD3004E6_L_1") (pin "4") (pinfunction "SINK_4") (pintype "output"))
      (node (ref "ZXGD3004E6_L_1") (pin "6") (pinfunction "SOURCE_6") (pintype "output"))
    )
    (net (code "74") (name "Net-(ZXGD3004E6_L_2-IN1)") (class "Default")
      (node (ref "R_INV_PD2") (pin "1") (pinfunction "1_1") (pintype "passive"))
      (node (ref "R_LIM_L_1_2") (pin "1") (pinfunction "1_1") (pintype "passive"))
      (node (ref "ZXGD3004E6_L_2") (pin "2") (pinfunction "IN1_2") (pintype "input"))
      (node (ref "ZXGD3004E6_L_2") (pin "5") (pinfunction "IN2_5") (pintype "input"))
    )
    (net (code "75") (name "Net-(ZXGD3004E6_L_2-SINK)") (class "Default")
      (node (ref "R_LIM_L_2_2") (pin "1") (pinfunction "1_1") (pintype "passive"))
      (node (ref "ZXGD3004E6_L_2") (pin "4") (pinfunction "SINK_4") (pintype "output"))
      (node (ref "ZXGD3004E6_L_2") (pin "6") (pinfunction "SOURCE_6") (pintype "output"))
    )
    (net (code "76") (name "Net-(ZXGD3004E6_L_3-IN1)") (class "Default")
      (node (ref "R_INV_PD3") (pin "1") (pinfunction "1_1") (pintype "passive"))
      (node (ref "R_LIM_L_1_3") (pin "1") (pinfunction "1_1") (pintype "passive"))
      (node (ref "ZXGD3004E6_L_3") (pin "2") (pinfunction "IN1_2") (pintype "input"))
      (node (ref "ZXGD3004E6_L_3") (pin "5") (pinfunction "IN2_5") (pintype "input"))
    )
    (net (code "77") (name "Net-(ZXGD3004E6_L_3-SINK)") (class "Default")
      (node (ref "R_LIM_L_2_3") (pin "1") (pinfunction "1_1") (pintype "passive"))
      (node (ref "ZXGD3004E6_L_3") (pin "4") (pinfunction "SINK_4") (pintype "output"))
      (node (ref "ZXGD3004E6_L_3") (pin "6") (pinfunction "SOURCE_6") (pintype "output"))
    )
    (net (code "78") (name "POS_PWM1") (class "Default")
      (node (ref "ENC1") (pin "12") (pinfunction "PWN_12") (pintype "passive"))
      (node (ref "IC7") (pin "13") (pinfunction "PA3-USART2RX/ADC3/SPI3MOSI/TIM2CH4_13") (pintype "bidirectional"))
      (node (ref "LED_POS1") (pin "C") (pinfunction "C_C") (pintype "passive"))
    )
    (net (code "79") (name "PWM_H_1") (class "Default")
      (node (ref "IC7") (pin "10") (pinfunction "PA0-USART2CTS/ADC0_10") (pintype "bidirectional"))
      (node (ref "R_LIM_H_1_1") (pin "2") (pinfunction "2_2") (pintype "passive"))
    )
    (net (code "80") (name "PWM_H_2") (class "Default")
      (node (ref "IC7") (pin "11") (pinfunction "PA1-USART2RTS/ADC1/SPI3SCK/TIM2CH2_11") (pintype "bidirectional"))
      (node (ref "R_LIM_H_1_2") (pin "2") (pinfunction "2_2") (pintype "passive"))
    )
    (net (code "81") (name "PWM_H_3") (class "Default")
      (node (ref "IC7") (pin "12") (pinfunction "PA2-USART2TX/ADC2/SPI3MISO/TIM2CH3_12") (pintype "bidirectional"))
      (node (ref "R_LIM_H_1_3") (pin "2") (pinfunction "2_2") (pintype "passive"))
    )
    (net (code "82") (name "PWM_L_1") (class "Default")
      (node (ref "IC7") (pin "42") (pinfunction "PB6-I2C1SCL+_42") (pintype "bidirectional"))
      (node (ref "R_LIM_L_1_1") (pin "2") (pinfunction "2_2") (pintype "passive"))
    )
    (net (code "83") (name "PWM_L_2") (class "Default")
      (node (ref "IC7") (pin "43") (pinfunction "PB7-I2C1SDA+_43") (pintype "bidirectional"))
      (node (ref "R_LIM_L_1_2") (pin "2") (pinfunction "2_2") (pintype "passive"))
    )
    (net (code "84") (name "PWM_L_3") (class "Default")
      (node (ref "IC7") (pin "45") (pinfunction "PB8-SPI2SCK/I2C1SCL+_45") (pintype "bidirectional"))
      (node (ref "R_LIM_L_1_3") (pin "2") (pinfunction "2_2") (pintype "passive"))
    )
    (net (code "85") (name "QEPA1") (class "Default")
      (node (ref "ENC1") (pin "3") (pinfunction "A_LSB_U_3") (pintype "output"))
      (node (ref "IC7") (pin "16") (pinfunction "PA6-SPI1MISO/ADC6/TIM3CH1_16") (pintype "bidirectional"))
    )
    (net (code "86") (name "QEPB1") (class "Default")
      (node (ref "ENC1") (pin "4") (pinfunction "B_DIR_V_4") (pintype "output"))
      (node (ref "IC7") (pin "14") (pinfunction "PA4-SPI1NSS/ADC4/SPI3NSS/USART2CK_14") (pintype "bidirectional"))
    )
    (net (code "87") (name "V+") (class "Default")
      (node (ref "C2") (pin "1") (pinfunction "1_1") (pintype "passive"))
      (node (ref "CIN1_1") (pin "1") (pinfunction "1_1") (pintype "passive"))
      (node (ref "CIN2_1") (pin "1") (pinfunction "1_1") (pintype "passive"))
      (node (ref "CS_1") (pin "P3") (pinfunction "V+_P3") (pintype "power_in"))
      (node (ref "CS_2") (pin "P3") (pinfunction "V+_P3") (pintype "power_in"))
      (node (ref "CS_3") (pin "P3") (pinfunction "V+_P3") (pintype "power_in"))
      (node (ref "C_CS_DC_1") (pin "1") (pinfunction "1_1") (pintype "passive"))
      (node (ref "C_CS_DC_2") (pin "1") (pinfunction "1_1") (pintype "passive"))
      (node (ref "C_CS_DC_3") (pin "1") (pinfunction "1_1") (pintype "passive"))
      (node (ref "D_INV_FB_H1") (pin "C") (pinfunction "C_C") (pintype "passive"))
      (node (ref "D_INV_FB_H2") (pin "C") (pinfunction "C_C") (pintype "passive"))
      (node (ref "D_INV_FB_H3") (pin "C") (pinfunction "C_C") (pintype "passive"))
      (node (ref "IC1") (pin "5") (pinfunction "VOUT_5") (pintype "bidirectional"))
      (node (ref "REG") (pin "3") (pinfunction "VIN_3") (pintype "input"))
      (node (ref "R_CS_4") (pin "1") (pinfunction "1_1") (pintype "passive"))
      (node (ref "R_INV_PU1") (pin "2") (pinfunction "2_2") (pintype "passive"))
      (node (ref "R_INV_PU2") (pin "2") (pinfunction "2_2") (pintype "passive"))
      (node (ref "R_INV_PU3") (pin "2") (pinfunction "2_2") (pintype "passive"))
      (node (ref "R_S1_1") (pin "2") (pinfunction "2_2") (pintype "passive"))
      (node (ref "R_V_SENSE_1_1") (pin "2") (pinfunction "2_2") (pintype "passive"))
      (node (ref "SW_REG1") (pin "11") (pinfunction "VIN_11") (pintype "bidirectional"))
      (node (ref "SW_REG1") (pin "2") (pinfunction "VIN_2") (pintype "bidirectional"))
      (node (ref "SW_REG1") (pin "3") (pinfunction "VIN_3") (pintype "bidirectional"))
      (node (ref "U$2") (pin "1") (pinfunction "S_1") (pintype "passive"))
      (node (ref "U$2") (pin "2") (pinfunction "S_2") (pintype "passive"))
      (node (ref "U$2") (pin "3") (pinfunction "S_3") (pintype "passive"))
      (node (ref "U$4") (pin "1") (pinfunction "S_1") (pintype "passive"))
      (node (ref "U$4") (pin "2") (pinfunction "S_2") (pintype "passive"))
      (node (ref "U$4") (pin "3") (pinfunction "S_3") (pintype "passive"))
      (node (ref "U$6") (pin "1") (pinfunction "S_1") (pintype "passive"))
      (node (ref "U$6") (pin "2") (pinfunction "S_2") (pintype "passive"))
      (node (ref "U$6") (pin "3") (pinfunction "S_3") (pintype "passive"))
      (node (ref "ZXGD3004E6_H_1") (pin "1") (pinfunction "VCC_1") (pintype "power_in"))
      (node (ref "ZXGD3004E6_H_2") (pin "1") (pinfunction "VCC_1") (pintype "power_in"))
      (node (ref "ZXGD3004E6_H_3") (pin "1") (pinfunction "VCC_1") (pintype "power_in"))
      (node (ref "ZXGD3004E6_L_1") (pin "1") (pinfunction "VCC_1") (pintype "power_in"))
      (node (ref "ZXGD3004E6_L_2") (pin "1") (pinfunction "VCC_1") (pintype "power_in"))
      (node (ref "ZXGD3004E6_L_3") (pin "1") (pinfunction "VCC_1") (pintype "power_in"))
    )
    (net (code "88") (name "V_BATT") (class "Default")
      (node (ref "CS_4") (pin "P3") (pinfunction "V+_P3") (pintype "power_in"))
      (node (ref "C_CS_DC_4") (pin "1") (pinfunction "1_1") (pintype "passive"))
      (node (ref "R_CS_4") (pin "2") (pinfunction "2_2") (pintype "passive"))
      (node (ref "R_S2_1") (pin "2") (pinfunction "2_2") (pintype "passive"))
      (node (ref "U$8") (pin "P$1") (pinfunction "1_P$1") (pintype "passive"))
    )
    (net (code "89") (name "V_REF_CS") (class "Default")
      (node (ref "CS_1") (pin "P1") (pinfunction "REF_P1") (pintype "input"))
      (node (ref "CS_2") (pin "P1") (pinfunction "REF_P1") (pintype "input"))
      (node (ref "CS_3") (pin "P1") (pinfunction "REF_P1") (pintype "input"))
      (node (ref "CS_4") (pin "P1") (pinfunction "REF_P1") (pintype "input"))
      (node (ref "R_CS_REF1_4") (pin "1") (pinfunction "1_1") (pintype "passive"))
      (node (ref "R_CS_REF2_4") (pin "2") (pinfunction "2_2") (pintype "passive"))
    )
    (net (code "90") (name "ZB_IRQ_1") (class "Default")
      (node (ref "IC7") (pin "4") (pinfunction "PC15-OSC32_OUT_4") (pintype "bidirectional"))
      (node (ref "RADIO1") (pin "24") (pinfunction "IRQ_24") (pintype "output"))
    )
    (net (code "91") (name "ZB_MISO_1") (class "Default")
      (node (ref "IC7") (pin "40") (pinfunction "PB4-SPI1MISO/SPI3MISO_40") (pintype "bidirectional"))
      (node (ref "RADIO1") (pin "20") (pinfunction "MISO_20") (pintype "output"))
    )
    (net (code "92") (name "ZB_MOSI_1") (class "Default")
      (node (ref "IC7") (pin "41") (pinfunction "PB5-SPI1MOSI/SPI3MOSI_41") (pintype "bidirectional"))
      (node (ref "RADIO1") (pin "22") (pinfunction "MOSI_22") (pintype "input"))
    )
    (net (code "93") (name "ZB_SCLK_1") (class "Default")
      (node (ref "IC7") (pin "39") (pinfunction "PB3-SPI1SCK/SPI3SCK_39") (pintype "bidirectional"))
      (node (ref "RADIO1") (pin "19") (pinfunction "SCLK_19") (pintype "input"))
    )
    (net (code "94") (name "ZB_SEL_1") (class "Default")
      (node (ref "IC7") (pin "3") (pinfunction "PC14-OSC32_IN_3") (pintype "bidirectional"))
      (node (ref "RADIO1") (pin "23") (pinfunction "\\SEL_23") (pintype "input"))
    )
    (net (code "95") (name "unconnected-(CN2-ID-Pad4)") (class "Default")
      (node (ref "CN2") (pin "4") (pinfunction "ID_4") (pintype "bidirectional"))
    )
    (net (code "96") (name "unconnected-(ENC1-CLK-Pad10)") (class "Default")
      (node (ref "ENC1") (pin "10") (pinfunction "CLK_10") (pintype "input"))
    )
    (net (code "97") (name "unconnected-(ENC1-COIL-Pad5)") (class "Default")
      (node (ref "ENC1") (pin "5") (pinfunction "COIL_5") (pintype "no_connect"))
    )
    (net (code "98") (name "unconnected-(ENC1-D0-Pad9)") (class "Default")
      (node (ref "ENC1") (pin "9") (pinfunction "D0_9") (pintype "tri_state"))
    )
    (net (code "99") (name "unconnected-(ENC1-T_B_0-Pad13)") (class "Default")
      (node (ref "ENC1") (pin "13") (pinfunction "T_B_0_13") (pintype "no_connect"))
    )
    (net (code "100") (name "unconnected-(ENC1-T_B_1-Pad14)") (class "Default")
      (node (ref "ENC1") (pin "14") (pinfunction "T_B_1_14") (pintype "no_connect"))
    )
    (net (code "101") (name "unconnected-(IC7-PB9-SPI2NSS{slash}I2C1SDA+-Pad46)") (class "Default")
      (node (ref "IC7") (pin "46") (pinfunction "PB9-SPI2NSS/I2C1SDA+_46") (pintype "bidirectional"))
    )
    (net (code "102") (name "unconnected-(IC7-PC13-TAMPER1-WKUP2-Pad2)") (class "Default")
      (node (ref "IC7") (pin "2") (pinfunction "PC13-TAMPER1-WKUP2_2") (pintype "bidirectional"))
    )
    (net (code "103") (name "unconnected-(IC7-PE9-Pad22)") (class "Default")
      (node (ref "IC7") (pin "22") (pinfunction "PE9_22") (pintype "bidirectional"))
    )
    (net (code "104") (name "unconnected-(RADIO1-CLKM-Pad17)") (class "Default")
      (node (ref "RADIO1") (pin "17") (pinfunction "CLKM_17") (pintype "output"))
    )
    (net (code "105") (name "unconnected-(RADIO1-DIG1-Pad9)") (class "Default")
      (node (ref "RADIO1") (pin "9") (pinfunction "DIG1_9") (pintype "output"))
    )
    (net (code "106") (name "unconnected-(RADIO1-DIG2-Pad10)") (class "Default")
      (node (ref "RADIO1") (pin "10") (pinfunction "DIG2_10") (pintype "output"))
    )
    (net (code "107") (name "unconnected-(RADIO1-DIG3-Pad1)") (class "Default")
      (node (ref "RADIO1") (pin "1") (pinfunction "DIG3_1") (pintype "output"))
    )
    (net (code "108") (name "unconnected-(RADIO1-DIG4-Pad2)") (class "Default")
      (node (ref "RADIO1") (pin "2") (pinfunction "DIG4_2") (pintype "output"))
    )
    (net (code "109") (name "unconnected-(RADIO1-XTAL2-Pad25)") (class "Default")
      (node (ref "RADIO1") (pin "25") (pinfunction "XTAL2_25") (pintype "bidirectional"))
    )
    (net (code "110") (name "unconnected-(SW_REG1-EN-Pad9)") (class "Default")
      (node (ref "SW_REG1") (pin "9") (pinfunction "EN_9") (pintype "bidirectional"))
    )
    (net (code "111") (name "unconnected-(SW_REG1-NC-Pad6)") (class "Default")
      (node (ref "SW_REG1") (pin "6") (pinfunction "NC_6") (pintype "no_connect"))
    )
    (net (code "112") (name "unconnected-(SW_REG1-NC2-Pad7)") (class "Default")
      (node (ref "SW_REG1") (pin "7") (pinfunction "NC2_7") (pintype "no_connect"))
    )
    (net (code "113") (name "unconnected-(SW_REG1-PG-Pad8)") (class "Default")
      (node (ref "SW_REG1") (pin "8") (pinfunction "PG_8") (pintype "bidirectional"))
    )
    (net (code "114") (name "unconnected-(U$10-AUX_CL-PadP$7)") (class "Default")
      (node (ref "U$10") (pin "P$7") (pinfunction "AUX_CL_P$7") (pintype "bidirectional"))
    )
    (net (code "115") (name "unconnected-(U$10-AUX_DA-PadP$6)") (class "Default")
      (node (ref "U$10") (pin "P$6") (pinfunction "AUX_DA_P$6") (pintype "bidirectional"))
    )
    (net (code "116") (name "unconnected-(U$10-CLKOUT-PadP$22)") (class "Default")
      (node (ref "U$10") (pin "P$22") (pinfunction "CLKOUT_P$22") (pintype "bidirectional"))
    )
  )
)
